# obc_old.net
KiCad netlist of a schematic drawn in EAGLE
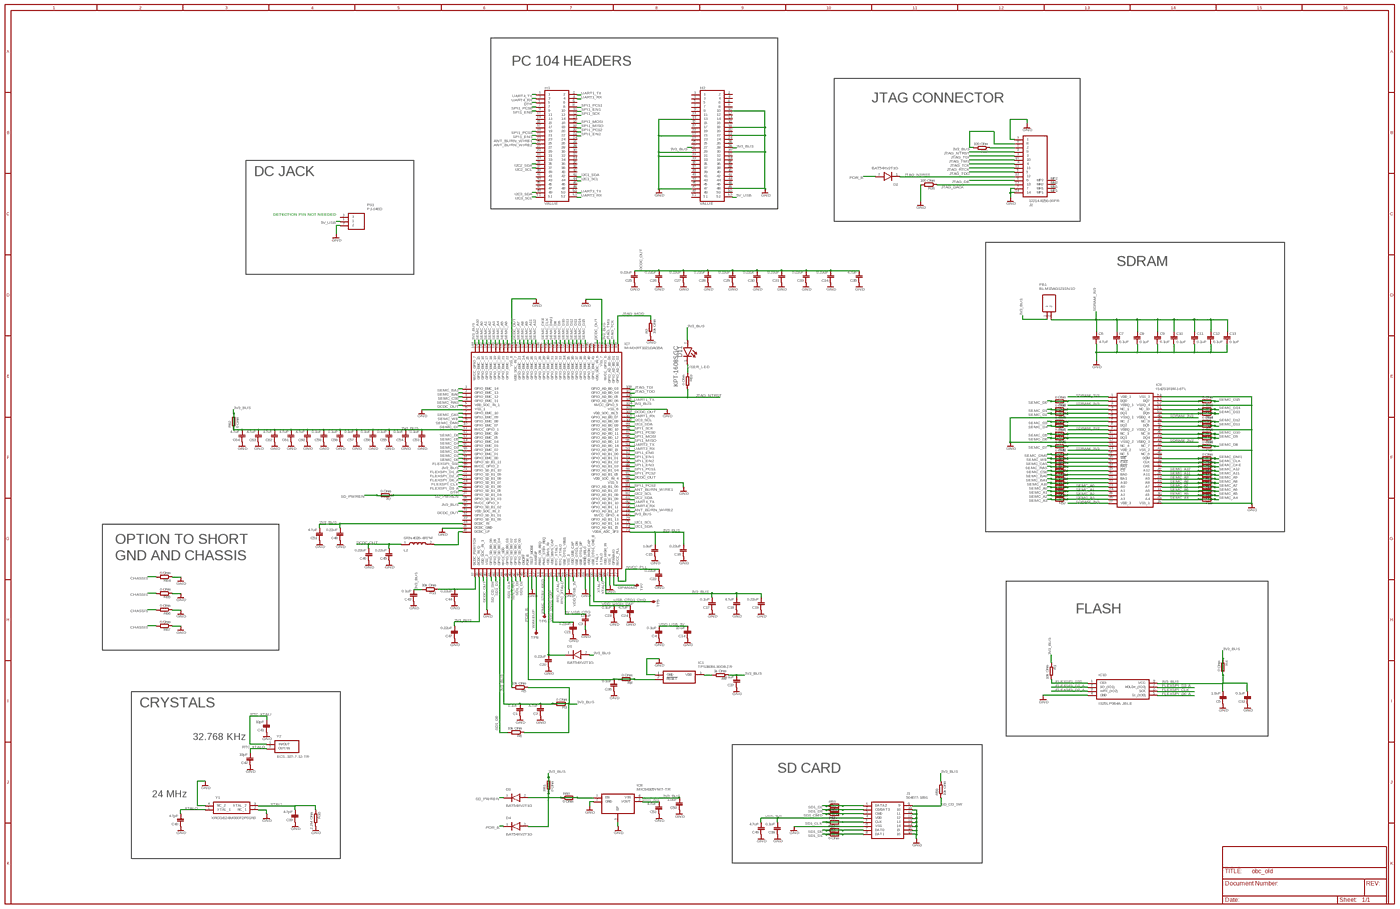
[diagram p0: schematic, sheet 1, overview]
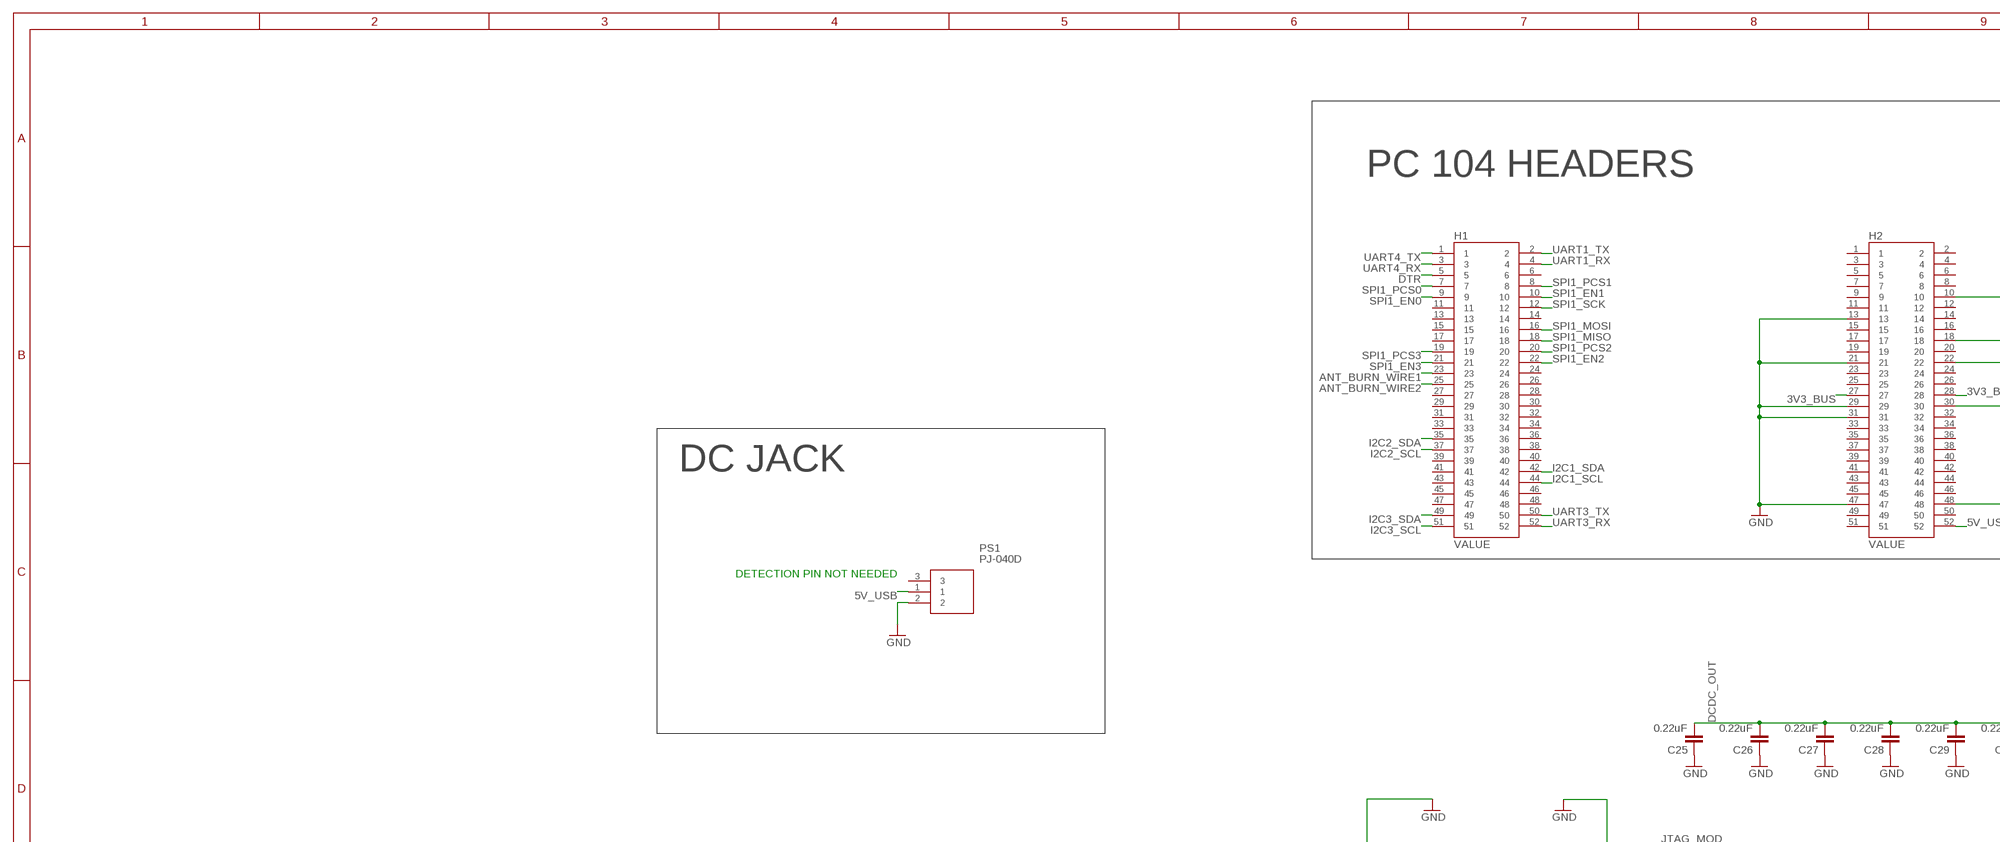
[diagram p1: schematic, sheet 1, part 1 of 4]
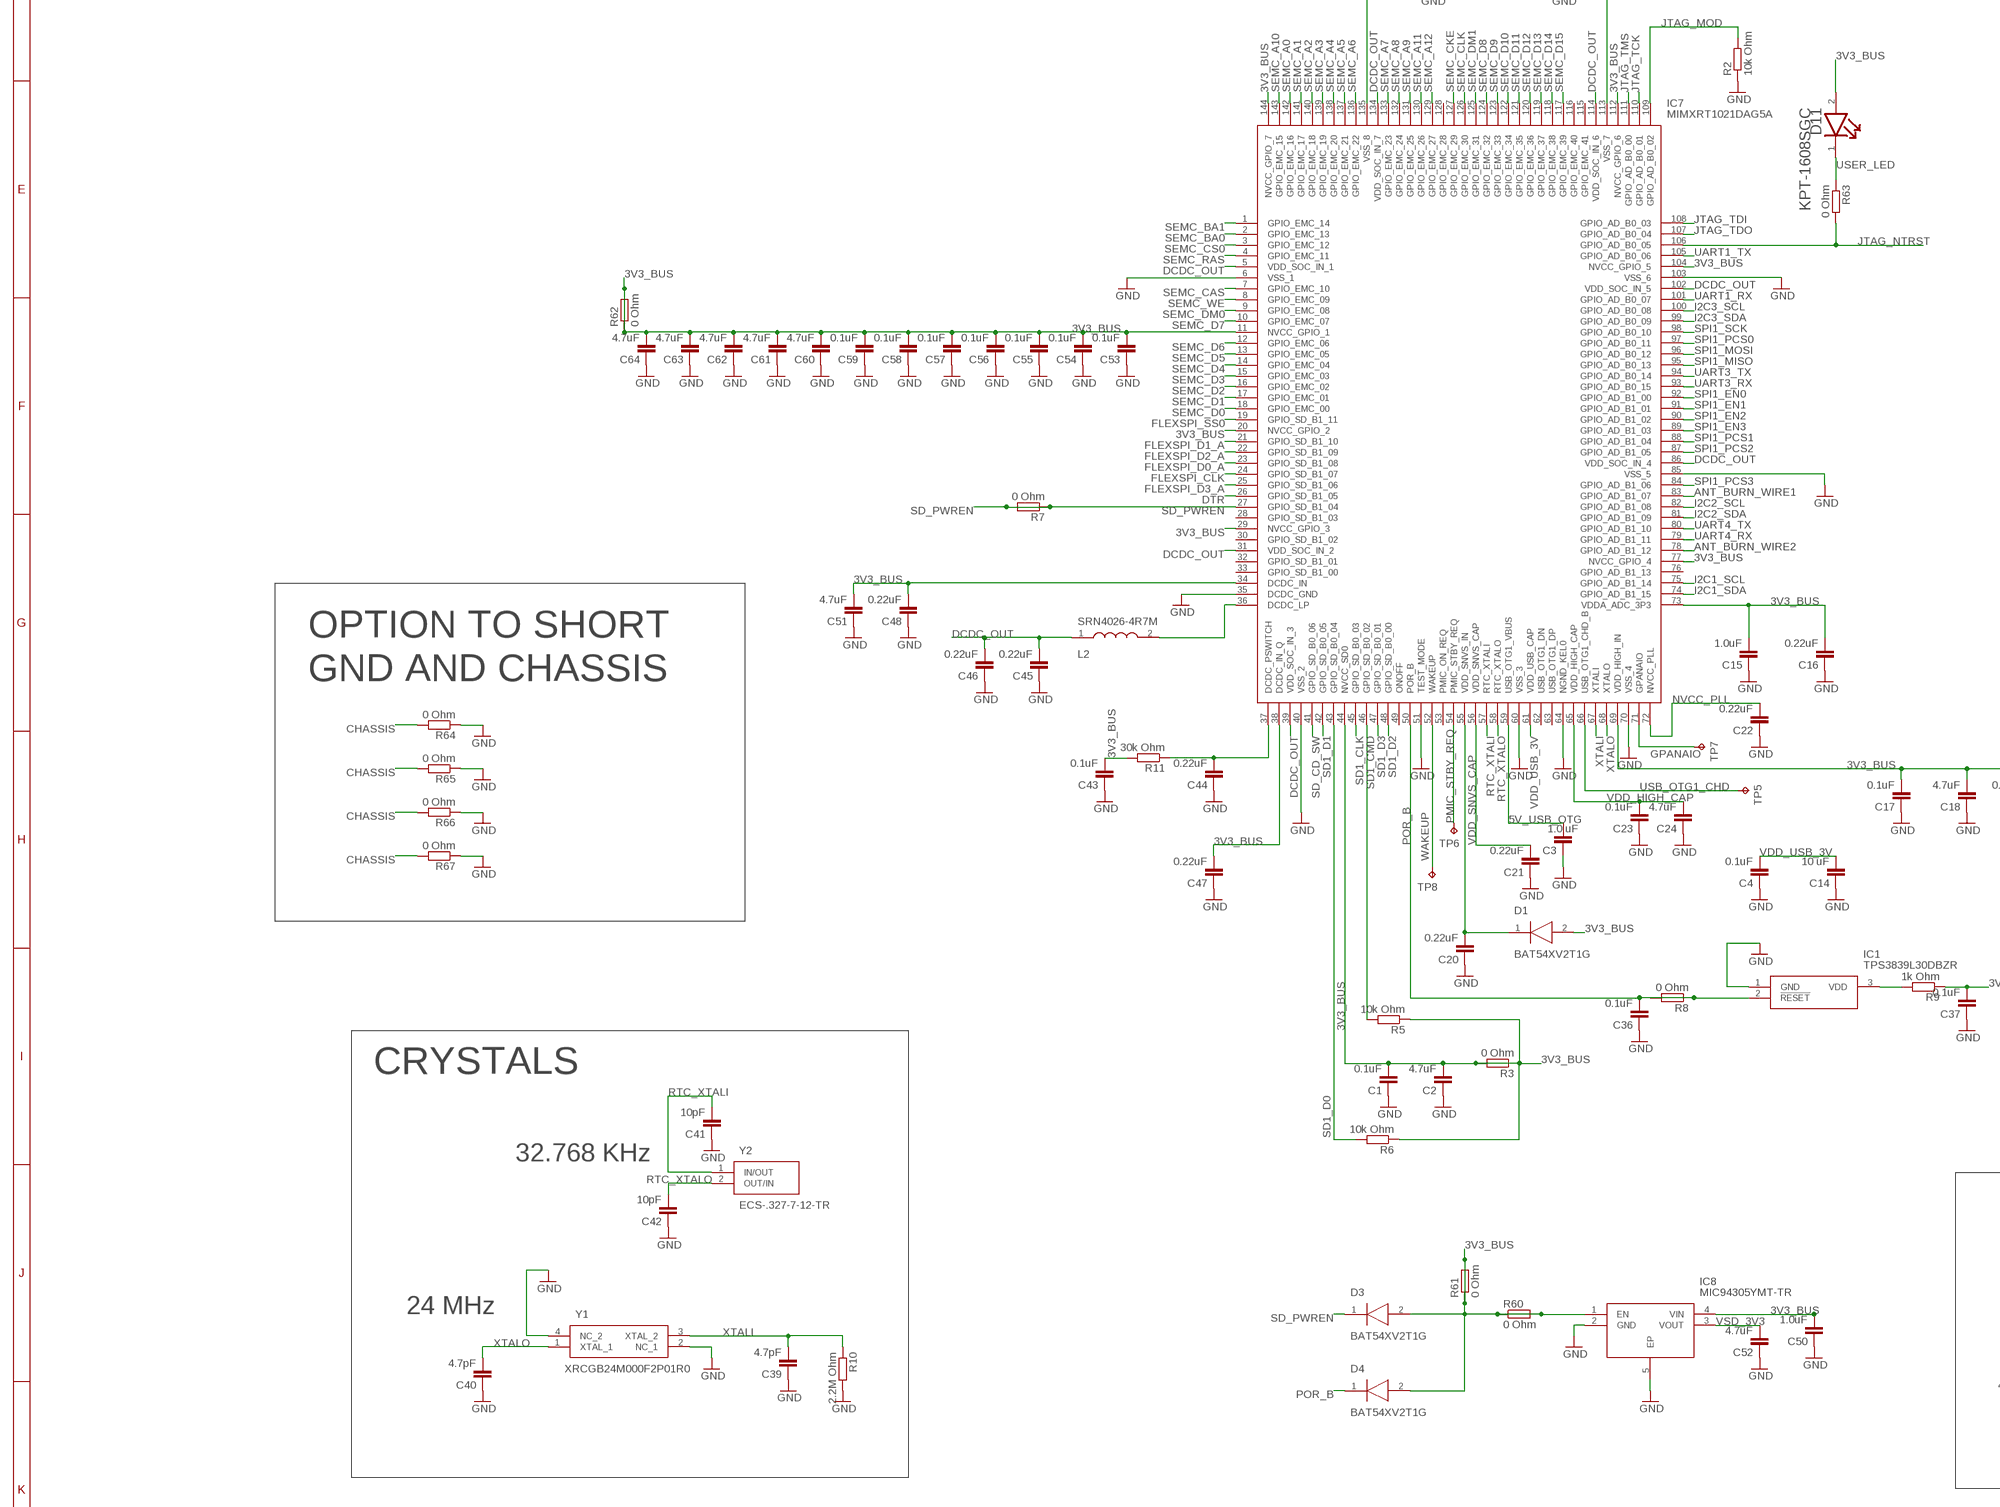
[diagram p2: schematic, sheet 1, part 2 of 4]
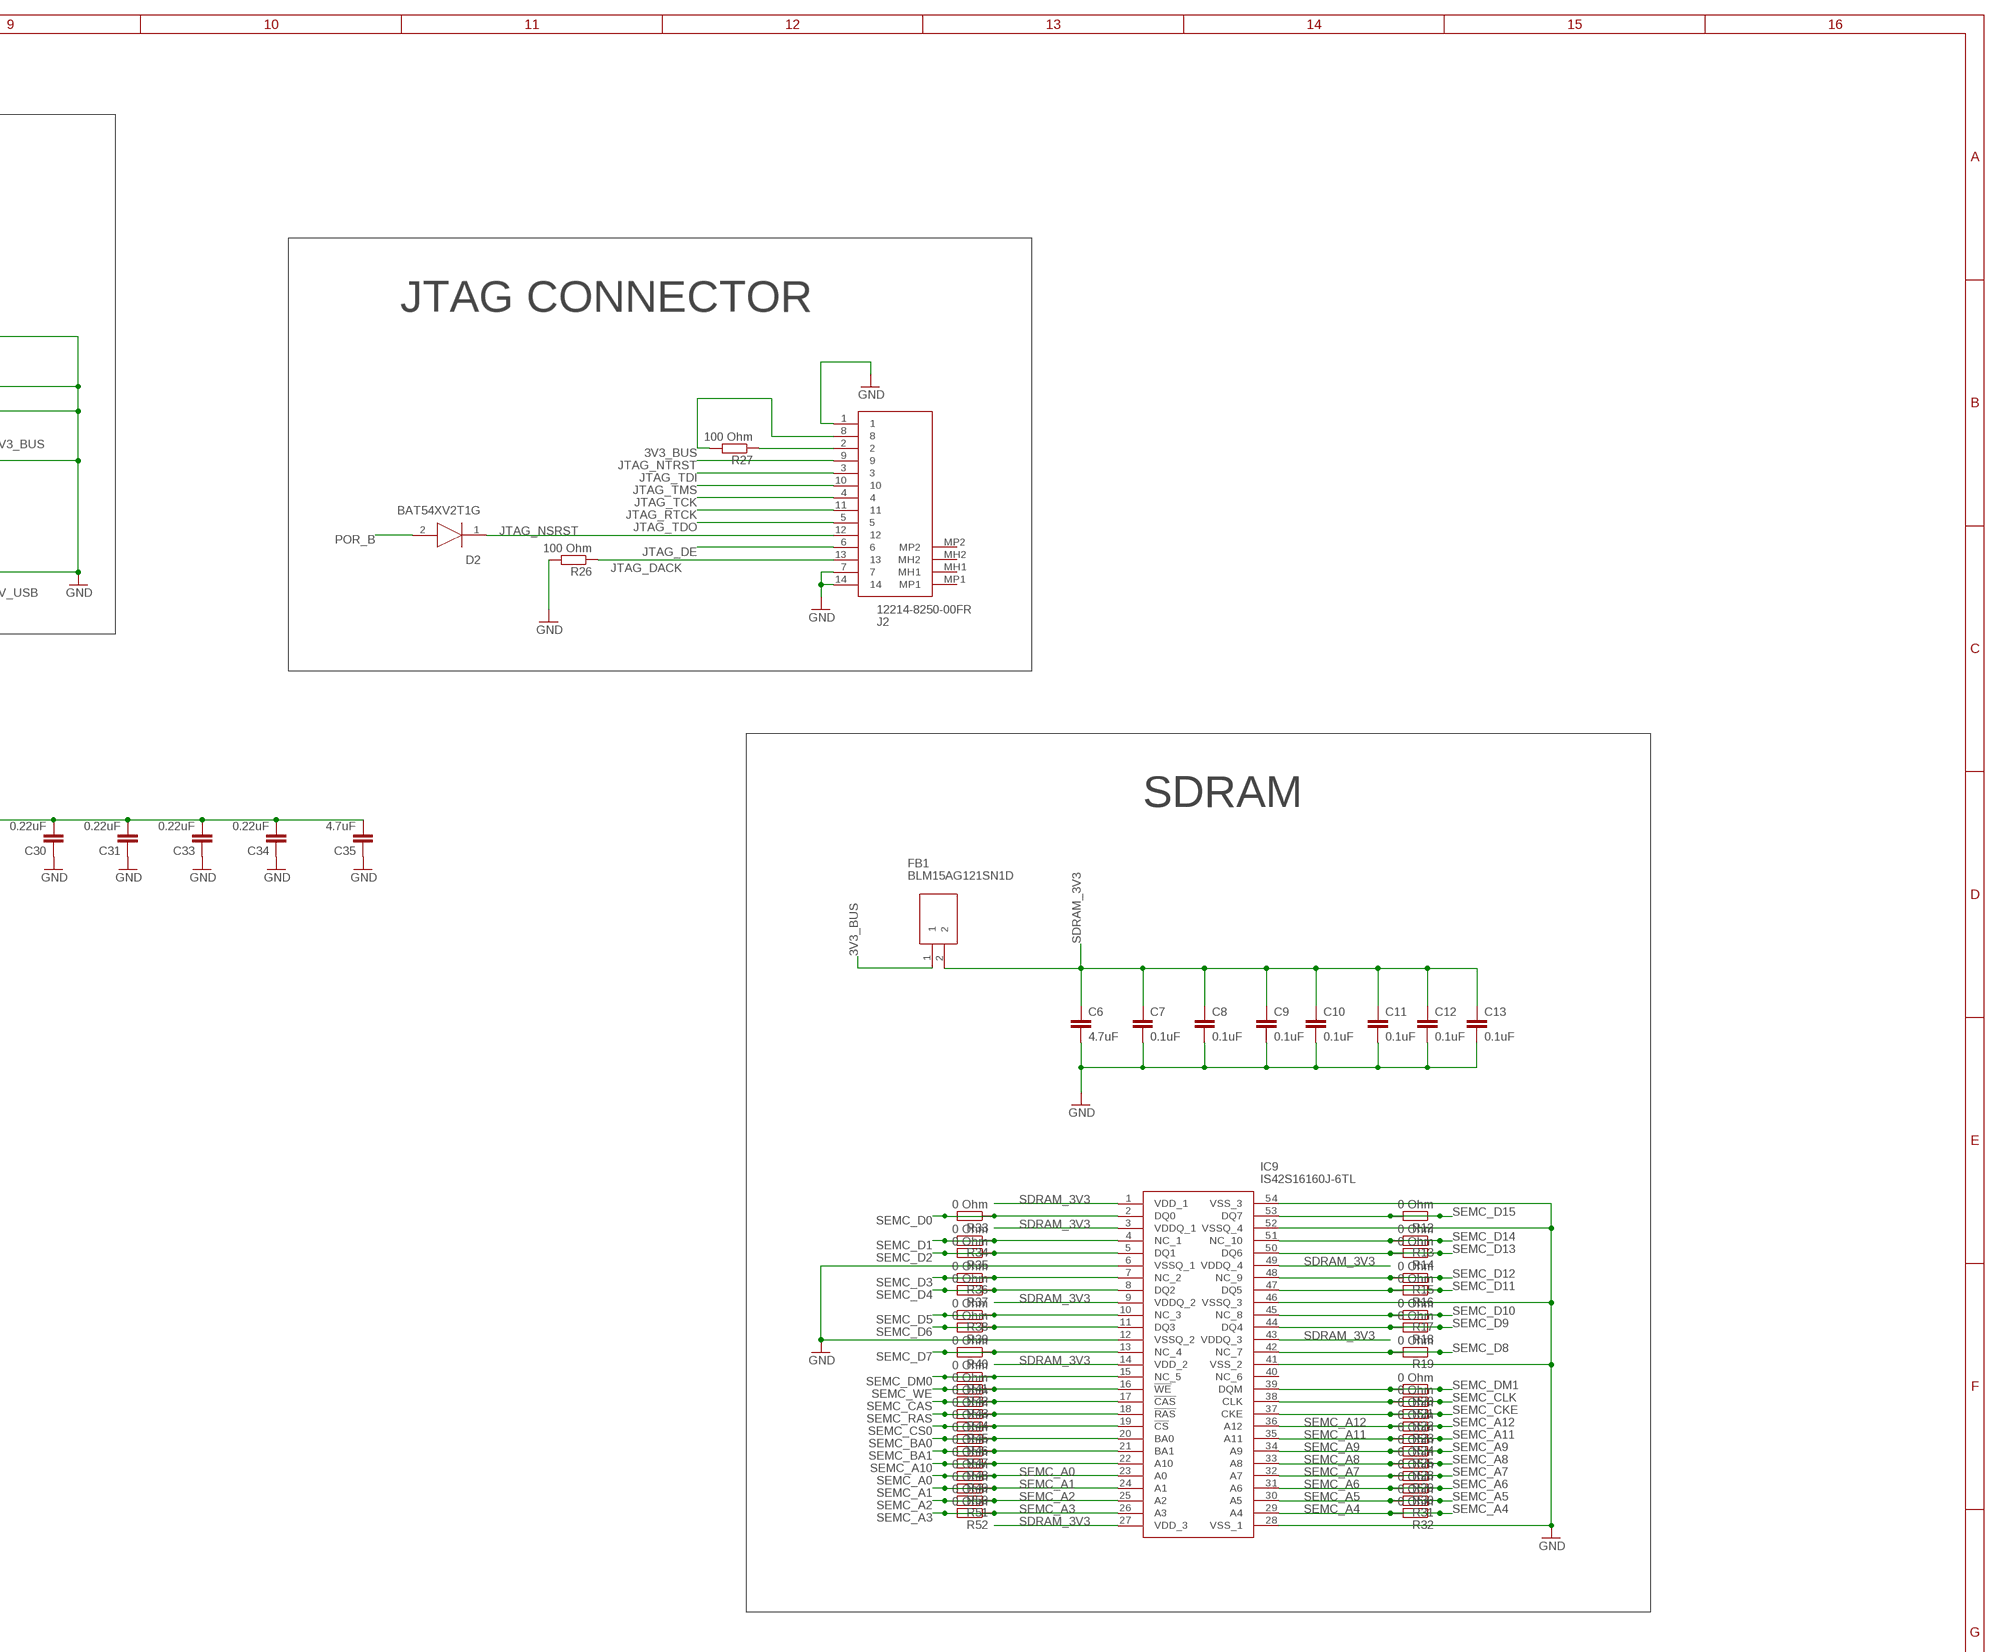
[diagram p3: schematic, sheet 1, part 3 of 4]
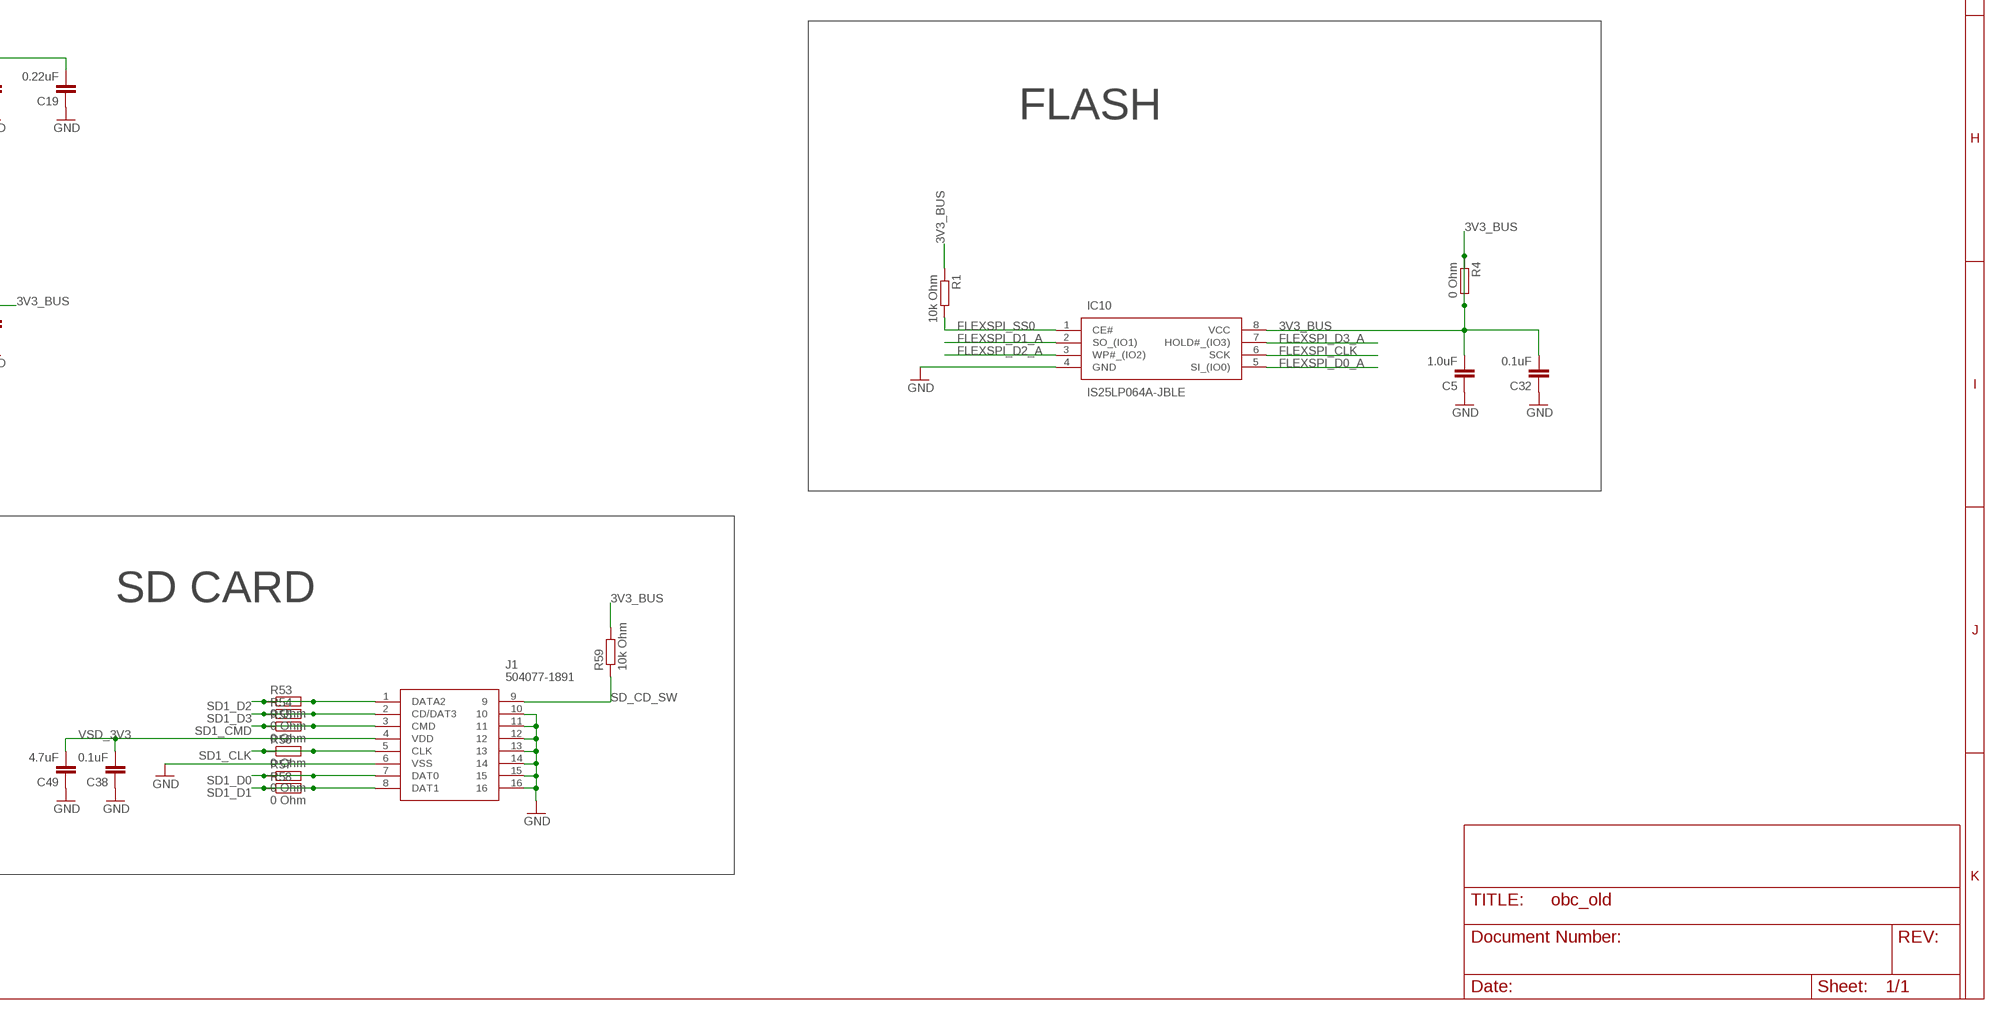
[diagram p4: schematic, sheet 1, part 4 of 4]

(export (version "E")
  (design (tool "Eeschema 10.0.6"))
  (components
    (comp (ref "C1")
      (value "0.1uF")
      (footprint "eagle-import:C0402K")
      (libsource (lib "eagle-import") (part "C-EUC0402K"))
    )
    (comp (ref "C2")
      (value "4.7uF")
      (footprint "eagle-import:C0402K")
      (libsource (lib "eagle-import") (part "C-EUC0402K"))
    )
    (comp (ref "C3")
      (value "1.0 uF")
      (footprint "eagle-import:C0402K")
      (libsource (lib "eagle-import") (part "C-EUC0402K"))
    )
    (comp (ref "C4")
      (value "0.1uF")
      (footprint "eagle-import:C0402K")
      (libsource (lib "eagle-import") (part "C-EUC0402K"))
    )
    (comp (ref "C5")
      (value "1.0uF")
      (footprint "eagle-import:C0402K")
      (libsource (lib "eagle-import") (part "C-EUC0402K"))
    )
    (comp (ref "C6")
      (value "4.7uF")
      (footprint "eagle-import:C0402K")
      (libsource (lib "eagle-import") (part "C-EUC0402K"))
    )
    (comp (ref "C7")
      (value "0.1uF")
      (footprint "eagle-import:C0402K")
      (libsource (lib "eagle-import") (part "C-EUC0402K"))
    )
    (comp (ref "C8")
      (value "0.1uF")
      (footprint "eagle-import:C0402K")
      (libsource (lib "eagle-import") (part "C-EUC0402K"))
    )
    (comp (ref "C9")
      (value "0.1uF")
      (footprint "eagle-import:C0402K")
      (libsource (lib "eagle-import") (part "C-EUC0402K"))
    )
    (comp (ref "C10")
      (value "0.1uF")
      (footprint "eagle-import:C0402K")
      (libsource (lib "eagle-import") (part "C-EUC0402K"))
    )
    (comp (ref "C11")
      (value "0.1uF")
      (footprint "eagle-import:C0402K")
      (libsource (lib "eagle-import") (part "C-EUC0402K"))
    )
    (comp (ref "C12")
      (value "0.1uF")
      (footprint "eagle-import:C0402K")
      (libsource (lib "eagle-import") (part "C-EUC0402K"))
    )
    (comp (ref "C13")
      (value "0.1uF")
      (footprint "eagle-import:C0402K")
      (libsource (lib "eagle-import") (part "C-EUC0402K"))
    )
    (comp (ref "C14")
      (value "10 uF")
      (footprint "eagle-import:C0402K")
      (libsource (lib "eagle-import") (part "C-EUC0402K"))
    )
    (comp (ref "C15")
      (value "1.0uF")
      (footprint "eagle-import:C0402K")
      (libsource (lib "eagle-import") (part "C-EUC0402K"))
    )
    (comp (ref "C16")
      (value "0.22uF")
      (footprint "eagle-import:C0402K")
      (libsource (lib "eagle-import") (part "C-EUC0402K"))
    )
    (comp (ref "C17")
      (value "0.1uF")
      (footprint "eagle-import:C0402K")
      (libsource (lib "eagle-import") (part "C-EUC0402K"))
    )
    (comp (ref "C18")
      (value "4.7uF")
      (footprint "eagle-import:C0402K")
      (libsource (lib "eagle-import") (part "C-EUC0402K"))
    )
    (comp (ref "C19")
      (value "0.22uF")
      (footprint "eagle-import:C0402K")
      (libsource (lib "eagle-import") (part "C-EUC0402K"))
    )
    (comp (ref "C20")
      (value "0.22uF")
      (footprint "eagle-import:C0402K")
      (libsource (lib "eagle-import") (part "C-EUC0402K"))
    )
    (comp (ref "C21")
      (value "0.22uF")
      (footprint "eagle-import:C0402K")
      (libsource (lib "eagle-import") (part "C-EUC0402K"))
    )
    (comp (ref "C22")
      (value "0.22uF")
      (footprint "eagle-import:C0402K")
      (libsource (lib "eagle-import") (part "C-EUC0402K"))
    )
    (comp (ref "C23")
      (value "0.1uF")
      (footprint "eagle-import:C0402K")
      (libsource (lib "eagle-import") (part "C-EUC0402K"))
    )
    (comp (ref "C24")
      (value "4.7uF")
      (footprint "eagle-import:C0402K")
      (libsource (lib "eagle-import") (part "C-EUC0402K"))
    )
    (comp (ref "C25")
      (value "0.22uF")
      (footprint "eagle-import:C0402K")
      (libsource (lib "eagle-import") (part "C-EUC0402K"))
    )
    (comp (ref "C26")
      (value "0.22uF")
      (footprint "eagle-import:C0402K")
      (libsource (lib "eagle-import") (part "C-EUC0402K"))
    )
    (comp (ref "C27")
      (value "0.22uF")
      (footprint "eagle-import:C0402K")
      (libsource (lib "eagle-import") (part "C-EUC0402K"))
    )
    (comp (ref "C28")
      (value "0.22uF")
      (footprint "eagle-import:C0402K")
      (libsource (lib "eagle-import") (part "C-EUC0402K"))
    )
    (comp (ref "C29")
      (value "0.22uF")
      (footprint "eagle-import:C0402K")
      (libsource (lib "eagle-import") (part "C-EUC0402K"))
    )
    (comp (ref "C30")
      (value "0.22uF")
      (footprint "eagle-import:C0402K")
      (libsource (lib "eagle-import") (part "C-EUC0402K"))
    )
    (comp (ref "C31")
      (value "0.22uF")
      (footprint "eagle-import:C0402K")
      (libsource (lib "eagle-import") (part "C-EUC0402K"))
    )
    (comp (ref "C32")
      (value "0.1uF")
      (footprint "eagle-import:C0402K")
      (libsource (lib "eagle-import") (part "C-EUC0402K"))
    )
    (comp (ref "C33")
      (value "0.22uF")
      (footprint "eagle-import:C0402K")
      (libsource (lib "eagle-import") (part "C-EUC0402K"))
    )
    (comp (ref "C34")
      (value "0.22uF")
      (footprint "eagle-import:C0402K")
      (libsource (lib "eagle-import") (part "C-EUC0402K"))
    )
    (comp (ref "C35")
      (value "4.7uF")
      (footprint "eagle-import:C0402K")
      (libsource (lib "eagle-import") (part "C-EUC0402K"))
    )
    (comp (ref "C36")
      (value "0.1uF")
      (footprint "eagle-import:C0402K")
      (libsource (lib "eagle-import") (part "C-EUC0402K"))
    )
    (comp (ref "C37")
      (value "0.1uF")
      (footprint "eagle-import:C0402K")
      (libsource (lib "eagle-import") (part "C-EUC0402K"))
    )
    (comp (ref "C38")
      (value "0.1uF")
      (footprint "eagle-import:C0402K")
      (libsource (lib "eagle-import") (part "C-EUC0402K"))
    )
    (comp (ref "C39")
      (value "4.7pF")
      (footprint "eagle-import:C0402K")
      (libsource (lib "eagle-import") (part "C-EUC0402K"))
    )
    (comp (ref "C40")
      (value "4.7pF")
      (footprint "eagle-import:C0402K")
      (libsource (lib "eagle-import") (part "C-EUC0402K"))
    )
    (comp (ref "C41")
      (value "10pF")
      (footprint "eagle-import:C0402K")
      (libsource (lib "eagle-import") (part "C-EUC0402K"))
    )
    (comp (ref "C42")
      (value "10pF")
      (footprint "eagle-import:C0402K")
      (libsource (lib "eagle-import") (part "C-EUC0402K"))
    )
    (comp (ref "C43")
      (value "0.1uF")
      (footprint "eagle-import:C0402K")
      (libsource (lib "eagle-import") (part "C-EUC0402K"))
    )
    (comp (ref "C44")
      (value "0.22uF")
      (footprint "eagle-import:C0402K")
      (libsource (lib "eagle-import") (part "C-EUC0402K"))
    )
    (comp (ref "C45")
      (value "0.22uF")
      (footprint "eagle-import:C0402K")
      (libsource (lib "eagle-import") (part "C-EUC0402K"))
    )
    (comp (ref "C46")
      (value "0.22uF")
      (footprint "eagle-import:C0402K")
      (libsource (lib "eagle-import") (part "C-EUC0402K"))
    )
    (comp (ref "C47")
      (value "0.22uF")
      (footprint "eagle-import:C0402K")
      (libsource (lib "eagle-import") (part "C-EUC0402K"))
    )
    (comp (ref "C48")
      (value "0.22uF")
      (footprint "eagle-import:C0402K")
      (libsource (lib "eagle-import") (part "C-EUC0402K"))
    )
    (comp (ref "C49")
      (value "4.7uF")
      (footprint "eagle-import:C0402K")
      (libsource (lib "eagle-import") (part "C-EUC0402K"))
    )
    (comp (ref "C50")
      (value "1.0uF")
      (footprint "eagle-import:C0402K")
      (libsource (lib "eagle-import") (part "C-EUC0402K"))
    )
    (comp (ref "C51")
      (value "4.7uF")
      (footprint "eagle-import:C0402K")
      (libsource (lib "eagle-import") (part "C-EUC0402K"))
    )
    (comp (ref "C52")
      (value "4.7uF")
      (footprint "eagle-import:C0402K")
      (libsource (lib "eagle-import") (part "C-EUC0402K"))
    )
    (comp (ref "C53")
      (value "0.1uF")
      (footprint "eagle-import:C0402K")
      (libsource (lib "eagle-import") (part "C-EUC0402K"))
    )
    (comp (ref "C54")
      (value "0.1uF")
      (footprint "eagle-import:C0402K")
      (libsource (lib "eagle-import") (part "C-EUC0402K"))
    )
    (comp (ref "C55")
      (value "0.1uF")
      (footprint "eagle-import:C0402K")
      (libsource (lib "eagle-import") (part "C-EUC0402K"))
    )
    (comp (ref "C56")
      (value "0.1uF")
      (footprint "eagle-import:C0402K")
      (libsource (lib "eagle-import") (part "C-EUC0402K"))
    )
    (comp (ref "C57")
      (value "0.1uF")
      (footprint "eagle-import:C0402K")
      (libsource (lib "eagle-import") (part "C-EUC0402K"))
    )
    (comp (ref "C58")
      (value "0.1uF")
      (footprint "eagle-import:C0402K")
      (libsource (lib "eagle-import") (part "C-EUC0402K"))
    )
    (comp (ref "C59")
      (value "0.1uF")
      (footprint "eagle-import:C0402K")
      (libsource (lib "eagle-import") (part "C-EUC0402K"))
    )
    (comp (ref "C60")
      (value "4.7uF")
      (footprint "eagle-import:C0402K")
      (libsource (lib "eagle-import") (part "C-EUC0402K"))
    )
    (comp (ref "C61")
      (value "4.7uF")
      (footprint "eagle-import:C0402K")
      (libsource (lib "eagle-import") (part "C-EUC0402K"))
    )
    (comp (ref "C62")
      (value "4.7uF")
      (footprint "eagle-import:C0402K")
      (libsource (lib "eagle-import") (part "C-EUC0402K"))
    )
    (comp (ref "C63")
      (value "4.7uF")
      (footprint "eagle-import:C0402K")
      (libsource (lib "eagle-import") (part "C-EUC0402K"))
    )
    (comp (ref "C64")
      (value "4.7uF")
      (footprint "eagle-import:C0402K")
      (libsource (lib "eagle-import") (part "C-EUC0402K"))
    )
    (comp (ref "D1")
      (value "BAT54XV2T1G")
      (footprint "eagle-import:SODFL1608X70N")
      (fields (field (name "MOUSER_PART_NUMBER") "863-BAT54XV2T1G"))
      (libsource (lib "eagle-import") (part "BAT54XV2T1G"))
    )
    (comp (ref "D2")
      (value "BAT54XV2T1G")
      (footprint "eagle-import:SODFL1608X70N")
      (fields (field (name "MOUSER_PART_NUMBER") "863-BAT54XV2T1G"))
      (libsource (lib "eagle-import") (part "BAT54XV2T1G"))
    )
    (comp (ref "D3")
      (value "BAT54XV2T1G")
      (footprint "eagle-import:SODFL1608X70N")
      (fields (field (name "MOUSER_PART_NUMBER") "863-BAT54XV2T1G"))
      (libsource (lib "eagle-import") (part "BAT54XV2T1G"))
    )
    (comp (ref "D4")
      (value "BAT54XV2T1G")
      (footprint "eagle-import:SODFL1608X70N")
      (fields (field (name "MOUSER_PART_NUMBER") "863-BAT54XV2T1G"))
      (libsource (lib "eagle-import") (part "BAT54XV2T1G"))
    )
    (comp (ref "D11")
      (value "KINGBRIGHT_KPT-1608SGCKINGBRIGHT_KPT-1608SGC_0_0")
      (footprint "eagle-import:KINGBRIGHT_KPT-1608SGC_0")
      (fields (field (name "MF") "Kingbright") (field (name "MPN") "KPT-1608SGC"))
      (libsource (lib "eagle-import") (part "KINGBRIGHT_KPT-1608SGCKINGBRIGHT_KPT-1608SGC_0_0"))
    )
    (comp (ref "FB1")
      (value "BLM15AG121SN1D")
      (footprint "eagle-import:NFZ15SG152SN10B")
      (fields (field (name "MOUSER_PART_NUMBER") "81-BLM15AG121SN1D"))
      (libsource (lib "eagle-import") (part "BLM15AG121SN1D"))
    )
    (comp (ref "H1")
      (value "ESQ-126-39-G-D")
      (footprint "eagle-import:SAMTEC_ESQ-126-39-G-D")
      (fields (field (name "DIGI-KEY_PART_NUMBER") "SAM10462-ND") (field (name "MF") "Samtec"))
      (libsource (lib "eagle-import") (part "ESQ-126-39-G-D"))
    )
    (comp (ref "H2")
      (value "ESQ-126-39-G-D")
      (footprint "eagle-import:SAMTEC_ESQ-126-39-G-D")
      (fields (field (name "DIGI-KEY_PART_NUMBER") "SAM10462-ND") (field (name "MF") "Samtec"))
      (libsource (lib "eagle-import") (part "ESQ-126-39-G-D"))
    )
    (comp (ref "IC1")
      (value "TPS3839L30DBZR")
      (footprint "eagle-import:SOT95P237X112-3N")
      (fields (field (name "MOUSER_PART_NUMBER") "595-TPS3839L30DBZR"))
      (libsource (lib "eagle-import") (part "TPS3839L30DBZR"))
    )
    (comp (ref "IC7")
      (value "MIMXRT1021DAG5A")
      (footprint "eagle-import:QFP50P2200X2200X160-144N")
      (fields (field (name "MOUSER_PART_NUMBER") "771-MIMXRT1021DAG5A"))
      (libsource (lib "eagle-import") (part "MIMXRT1021DAG5A"))
    )
    (comp (ref "IC8")
      (value "MIC94305YMT-TR")
      (footprint "eagle-import:SON50P160X120X60-5N")
      (fields (field (name "MOUSER_PART_NUMBER") "998-MIC94305YMTTR"))
      (libsource (lib "eagle-import") (part "MIC94305YMT-TR"))
    )
    (comp (ref "IC9")
      (value "IS42S16160J-6TL")
      (footprint "eagle-import:SOP80P1176X120-54N")
      (fields (field (name "MOUSER_PART_NUMBER") "870-IS42S16160J-6TL"))
      (libsource (lib "eagle-import") (part "IS42S16160J-6TL"))
    )
    (comp (ref "IC10")
      (value "IS25LP064A-JBLE")
      (footprint "eagle-import:SOIC127P790X216-8N")
      (libsource (lib "eagle-import") (part "IS25LP064A-JBLE"))
    )
    (comp (ref "J1")
      (value "504077-1891")
      (footprint "eagle-import:5040771891")
      (fields (field (name "MOUSER_PART_NUMBER") "538-504077-1891"))
      (libsource (lib "eagle-import") (part "504077-1891"))
    )
    (comp (ref "J2")
      (value "12214-8250-00FR")
      (footprint "eagle-import:12214825000FR")
      (fields (field (name "MOUSER_PART_NUMBER") "517-12214-825000FR"))
      (libsource (lib "eagle-import") (part "12214-8250-00FR"))
    )
    (comp (ref "L2")
      (value "SRN4026-4R7M")
      (footprint "eagle-import:SRN4026")
      (fields (field (name "MOUSER_PART_NUMBER") "652-SRN4026-4R7M"))
      (libsource (lib "eagle-import") (part "SRN4026-4R7M"))
    )
    (comp (ref "PS1")
      (value "PJ-040D")
      (footprint "eagle-import:PJ040D")
      (fields (field (name "MOUSER_PART_NUMBER") "490-PJ-040D"))
      (libsource (lib "eagle-import") (part "PJ-040D"))
    )
    (comp (ref "R1")
      (value "10k Ohm")
      (footprint "eagle-import:R0402")
      (libsource (lib "eagle-import") (part "R-EU_R0402"))
    )
    (comp (ref "R2")
      (value "10k Ohm")
      (footprint "eagle-import:R0402")
      (libsource (lib "eagle-import") (part "R-EU_R0402"))
    )
    (comp (ref "R3")
      (value "0 Ohm")
      (footprint "eagle-import:R0402")
      (libsource (lib "eagle-import") (part "R-EU_R0402"))
    )
    (comp (ref "R4")
      (value "0 Ohm")
      (footprint "eagle-import:R0402")
      (libsource (lib "eagle-import") (part "R-EU_R0402"))
    )
    (comp (ref "R5")
      (value "10k Ohm")
      (footprint "eagle-import:R0402")
      (libsource (lib "eagle-import") (part "R-EU_R0402"))
    )
    (comp (ref "R6")
      (value "10k Ohm")
      (footprint "eagle-import:R0402")
      (libsource (lib "eagle-import") (part "R-EU_R0402"))
    )
    (comp (ref "R7")
      (value "0 Ohm")
      (footprint "eagle-import:R0402")
      (libsource (lib "eagle-import") (part "R-EU_R0402"))
    )
    (comp (ref "R8")
      (value "0 Ohm")
      (footprint "eagle-import:R0402")
      (libsource (lib "eagle-import") (part "R-EU_R0402"))
    )
    (comp (ref "R9")
      (value "1k Ohm")
      (footprint "eagle-import:R0402")
      (libsource (lib "eagle-import") (part "R-EU_R0402"))
    )
    (comp (ref "R10")
      (value "2.2M Ohm")
      (footprint "eagle-import:R0402")
      (libsource (lib "eagle-import") (part "R-EU_R0402"))
    )
    (comp (ref "R11")
      (value "30k Ohm")
      (footprint "eagle-import:R0402")
      (libsource (lib "eagle-import") (part "R-EU_R0402"))
    )
    (comp (ref "R12")
      (value "0 Ohm")
      (footprint "eagle-import:R0402")
      (libsource (lib "eagle-import") (part "R-EU_R0402"))
    )
    (comp (ref "R13")
      (value "0 Ohm")
      (footprint "eagle-import:R0402")
      (libsource (lib "eagle-import") (part "R-EU_R0402"))
    )
    (comp (ref "R14")
      (value "0 Ohm")
      (footprint "eagle-import:R0402")
      (libsource (lib "eagle-import") (part "R-EU_R0402"))
    )
    (comp (ref "R15")
      (value "0 Ohm")
      (footprint "eagle-import:R0402")
      (libsource (lib "eagle-import") (part "R-EU_R0402"))
    )
    (comp (ref "R16")
      (value "0 Ohm")
      (footprint "eagle-import:R0402")
      (libsource (lib "eagle-import") (part "R-EU_R0402"))
    )
    (comp (ref "R17")
      (value "0 Ohm")
      (footprint "eagle-import:R0402")
      (libsource (lib "eagle-import") (part "R-EU_R0402"))
    )
    (comp (ref "R18")
      (value "0 Ohm")
      (footprint "eagle-import:R0402")
      (libsource (lib "eagle-import") (part "R-EU_R0402"))
    )
    (comp (ref "R19")
      (value "0 Ohm")
      (footprint "eagle-import:R0402")
      (libsource (lib "eagle-import") (part "R-EU_R0402"))
    )
    (comp (ref "R20")
      (value "0 Ohm")
      (footprint "eagle-import:R0402")
      (libsource (lib "eagle-import") (part "R-EU_R0402"))
    )
    (comp (ref "R21")
      (value "0 Ohm")
      (footprint "eagle-import:R0402")
      (libsource (lib "eagle-import") (part "R-EU_R0402"))
    )
    (comp (ref "R22")
      (value "0 Ohm")
      (footprint "eagle-import:R0402")
      (libsource (lib "eagle-import") (part "R-EU_R0402"))
    )
    (comp (ref "R23")
      (value "0 Ohm")
      (footprint "eagle-import:R0402")
      (libsource (lib "eagle-import") (part "R-EU_R0402"))
    )
    (comp (ref "R24")
      (value "0 Ohm")
      (footprint "eagle-import:R0402")
      (libsource (lib "eagle-import") (part "R-EU_R0402"))
    )
    (comp (ref "R25")
      (value "0 Ohm")
      (footprint "eagle-import:R0402")
      (libsource (lib "eagle-import") (part "R-EU_R0402"))
    )
    (comp (ref "R26")
      (value "100 Ohm")
      (footprint "eagle-import:R0402")
      (libsource (lib "eagle-import") (part "R-EU_R0402"))
    )
    (comp (ref "R27")
      (value "100 Ohm")
      (footprint "eagle-import:R0402")
      (libsource (lib "eagle-import") (part "R-EU_R0402"))
    )
    (comp (ref "R28")
      (value "0 Ohm")
      (footprint "eagle-import:R0402")
      (libsource (lib "eagle-import") (part "R-EU_R0402"))
    )
    (comp (ref "R29")
      (value "0 Ohm")
      (footprint "eagle-import:R0402")
      (libsource (lib "eagle-import") (part "R-EU_R0402"))
    )
    (comp (ref "R30")
      (value "0 Ohm")
      (footprint "eagle-import:R0402")
      (libsource (lib "eagle-import") (part "R-EU_R0402"))
    )
    (comp (ref "R31")
      (value "0 Ohm")
      (footprint "eagle-import:R0402")
      (libsource (lib "eagle-import") (part "R-EU_R0402"))
    )
    (comp (ref "R32")
      (value "0 Ohm")
      (footprint "eagle-import:R0402")
      (libsource (lib "eagle-import") (part "R-EU_R0402"))
    )
    (comp (ref "R33")
      (value "0 Ohm")
      (footprint "eagle-import:R0402")
      (libsource (lib "eagle-import") (part "R-EU_R0402"))
    )
    (comp (ref "R34")
      (value "0 Ohm")
      (footprint "eagle-import:R0402")
      (libsource (lib "eagle-import") (part "R-EU_R0402"))
    )
    (comp (ref "R35")
      (value "0 Ohm")
      (footprint "eagle-import:R0402")
      (libsource (lib "eagle-import") (part "R-EU_R0402"))
    )
    (comp (ref "R36")
      (value "0 Ohm")
      (footprint "eagle-import:R0402")
      (libsource (lib "eagle-import") (part "R-EU_R0402"))
    )
    (comp (ref "R37")
      (value "0 Ohm")
      (footprint "eagle-import:R0402")
      (libsource (lib "eagle-import") (part "R-EU_R0402"))
    )
    (comp (ref "R38")
      (value "0 Ohm")
      (footprint "eagle-import:R0402")
      (libsource (lib "eagle-import") (part "R-EU_R0402"))
    )
    (comp (ref "R39")
      (value "0 Ohm")
      (footprint "eagle-import:R0402")
      (libsource (lib "eagle-import") (part "R-EU_R0402"))
    )
    (comp (ref "R40")
      (value "0 Ohm")
      (footprint "eagle-import:R0402")
      (libsource (lib "eagle-import") (part "R-EU_R0402"))
    )
    (comp (ref "R41")
      (value "0 Ohm")
      (footprint "eagle-import:R0402")
      (libsource (lib "eagle-import") (part "R-EU_R0402"))
    )
    (comp (ref "R42")
      (value "0 Ohm")
      (footprint "eagle-import:R0402")
      (libsource (lib "eagle-import") (part "R-EU_R0402"))
    )
    (comp (ref "R43")
      (value "0 Ohm")
      (footprint "eagle-import:R0402")
      (libsource (lib "eagle-import") (part "R-EU_R0402"))
    )
    (comp (ref "R44")
      (value "0 Ohm")
      (footprint "eagle-import:R0402")
      (libsource (lib "eagle-import") (part "R-EU_R0402"))
    )
    (comp (ref "R45")
      (value "0 Ohm")
      (footprint "eagle-import:R0402")
      (libsource (lib "eagle-import") (part "R-EU_R0402"))
    )
    (comp (ref "R46")
      (value "0 Ohm")
      (footprint "eagle-import:R0402")
      (libsource (lib "eagle-import") (part "R-EU_R0402"))
    )
    (comp (ref "R47")
      (value "0 Ohm")
      (footprint "eagle-import:R0402")
      (libsource (lib "eagle-import") (part "R-EU_R0402"))
    )
    (comp (ref "R48")
      (value "0 Ohm")
      (footprint "eagle-import:R0402")
      (libsource (lib "eagle-import") (part "R-EU_R0402"))
    )
    (comp (ref "R49")
      (value "0 Ohm")
      (footprint "eagle-import:R0402")
      (libsource (lib "eagle-import") (part "R-EU_R0402"))
    )
    (comp (ref "R50")
      (value "0 Ohm")
      (footprint "eagle-import:R0402")
      (libsource (lib "eagle-import") (part "R-EU_R0402"))
    )
    (comp (ref "R51")
      (value "0 Ohm")
      (footprint "eagle-import:R0402")
      (libsource (lib "eagle-import") (part "R-EU_R0402"))
    )
    (comp (ref "R52")
      (value "0 Ohm")
      (footprint "eagle-import:R0402")
      (libsource (lib "eagle-import") (part "R-EU_R0402"))
    )
    (comp (ref "R53")
      (value "0 Ohm")
      (footprint "eagle-import:R0402")
      (libsource (lib "eagle-import") (part "R-EU_R0402"))
    )
    (comp (ref "R54")
      (value "0 Ohm")
      (footprint "eagle-import:R0402")
      (libsource (lib "eagle-import") (part "R-EU_R0402"))
    )
    (comp (ref "R55")
      (value "0 Ohm")
      (footprint "eagle-import:R0402")
      (libsource (lib "eagle-import") (part "R-EU_R0402"))
    )
    (comp (ref "R56")
      (value "0 Ohm")
      (footprint "eagle-import:R0402")
      (libsource (lib "eagle-import") (part "R-EU_R0402"))
    )
    (comp (ref "R57")
      (value "0 Ohm")
      (footprint "eagle-import:R0402")
      (libsource (lib "eagle-import") (part "R-EU_R0402"))
    )
    (comp (ref "R58")
      (value "0 Ohm")
      (footprint "eagle-import:R0402")
      (libsource (lib "eagle-import") (part "R-EU_R0402"))
    )
    (comp (ref "R59")
      (value "10k Ohm")
      (footprint "eagle-import:R0402")
      (libsource (lib "eagle-import") (part "R-EU_R0402"))
    )
    (comp (ref "R60")
      (value "0 Ohm")
      (footprint "eagle-import:R0402")
      (libsource (lib "eagle-import") (part "R-EU_R0402"))
    )
    (comp (ref "R61")
      (value "0 Ohm")
      (footprint "eagle-import:R0402")
      (libsource (lib "eagle-import") (part "R-EU_R0402"))
    )
    (comp (ref "R62")
      (value "0 Ohm")
      (footprint "eagle-import:R0402")
      (libsource (lib "eagle-import") (part "R-EU_R0402"))
    )
    (comp (ref "R63")
      (value "0 Ohm")
      (footprint "eagle-import:R0402")
      (libsource (lib "eagle-import") (part "R-EU_R0402"))
    )
    (comp (ref "R64")
      (value "0 Ohm")
      (footprint "eagle-import:R0402")
      (libsource (lib "eagle-import") (part "R-EU_R0402"))
    )
    (comp (ref "R65")
      (value "0 Ohm")
      (footprint "eagle-import:R0402")
      (libsource (lib "eagle-import") (part "R-EU_R0402"))
    )
    (comp (ref "R66")
      (value "0 Ohm")
      (footprint "eagle-import:R0402")
      (libsource (lib "eagle-import") (part "R-EU_R0402"))
    )
    (comp (ref "R67")
      (value "0 Ohm")
      (footprint "eagle-import:R0402")
      (libsource (lib "eagle-import") (part "R-EU_R0402"))
    )
    (comp (ref "TP5")
      (value "TPTP06R")
      (footprint "eagle-import:TP06R")
      (libsource (lib "eagle-import") (part "TPTP06R"))
    )
    (comp (ref "TP6")
      (value "TPTP06R")
      (footprint "eagle-import:TP06R")
      (libsource (lib "eagle-import") (part "TPTP06R"))
    )
    (comp (ref "TP7")
      (value "TPTP06R")
      (footprint "eagle-import:TP06R")
      (libsource (lib "eagle-import") (part "TPTP06R"))
    )
    (comp (ref "TP8")
      (value "TPTP06R")
      (footprint "eagle-import:TP06R")
      (libsource (lib "eagle-import") (part "TPTP06R"))
    )
    (comp (ref "Y1")
      (value "XRCGB24M000F2P01R0")
      (footprint "eagle-import:XRCGB24M000F2P01R0")
      (fields (field (name "MOUSER_PART_NUMBER") "81-XRCGB24M000F2P01R"))
      (libsource (lib "eagle-import") (part "XRCGB24M000F2P01R0"))
    )
    (comp (ref "Y2")
      (value "ECS-.327-7-12-TR")
      (footprint "eagle-import:ECS327712TR")
      (fields (field (name "MOUSER_PART_NUMBER") "520-ECS-.327-7-12-TR"))
      (libsource (lib "eagle-import") (part "ECS-.327-7-12-TR"))
    )
  )
  (nets
    (net (code "1") (name "/3V3_BUS") (class "Default")
      (node (ref "C1") (pin "2") (pinfunction "2_2") (pintype "passive"))
      (node (ref "C15") (pin "2") (pinfunction "2_2") (pintype "passive"))
      (node (ref "C16") (pin "2") (pinfunction "2_2") (pintype "passive"))
      (node (ref "C17") (pin "2") (pinfunction "2_2") (pintype "passive"))
      (node (ref "C18") (pin "2") (pinfunction "2_2") (pintype "passive"))
      (node (ref "C19") (pin "2") (pinfunction "2_2") (pintype "passive"))
      (node (ref "C2") (pin "2") (pinfunction "2_2") (pintype "passive"))
      (node (ref "C32") (pin "2") (pinfunction "2_2") (pintype "passive"))
      (node (ref "C37") (pin "2") (pinfunction "2_2") (pintype "passive"))
      (node (ref "C43") (pin "2") (pinfunction "2_2") (pintype "passive"))
      (node (ref "C47") (pin "2") (pinfunction "2_2") (pintype "passive"))
      (node (ref "C48") (pin "2") (pinfunction "2_2") (pintype "passive"))
      (node (ref "C5") (pin "2") (pinfunction "2_2") (pintype "passive"))
      (node (ref "C50") (pin "2") (pinfunction "2_2") (pintype "passive"))
      (node (ref "C51") (pin "2") (pinfunction "2_2") (pintype "passive"))
      (node (ref "C53") (pin "2") (pinfunction "2_2") (pintype "passive"))
      (node (ref "C54") (pin "2") (pinfunction "2_2") (pintype "passive"))
      (node (ref "C55") (pin "2") (pinfunction "2_2") (pintype "passive"))
      (node (ref "C56") (pin "2") (pinfunction "2_2") (pintype "passive"))
      (node (ref "C57") (pin "2") (pinfunction "2_2") (pintype "passive"))
      (node (ref "C58") (pin "2") (pinfunction "2_2") (pintype "passive"))
      (node (ref "C59") (pin "2") (pinfunction "2_2") (pintype "passive"))
      (node (ref "C60") (pin "2") (pinfunction "2_2") (pintype "passive"))
      (node (ref "C61") (pin "2") (pinfunction "2_2") (pintype "passive"))
      (node (ref "C62") (pin "2") (pinfunction "2_2") (pintype "passive"))
      (node (ref "C63") (pin "2") (pinfunction "2_2") (pintype "passive"))
      (node (ref "C64") (pin "2") (pinfunction "2_2") (pintype "passive"))
      (node (ref "D1") (pin "2") (pinfunction "A_2") (pintype "bidirectional"))
      (node (ref "D11") (pin "2") (pinfunction "ANODE_2") (pintype "passive"))
      (node (ref "D3") (pin "2") (pinfunction "A_2") (pintype "bidirectional"))
      (node (ref "D4") (pin "2") (pinfunction "A_2") (pintype "bidirectional"))
      (node (ref "FB1") (pin "1") (pinfunction "1_1") (pintype "bidirectional"))
      (node (ref "H2") (pin "27") (pinfunction "27_27") (pintype "passive"))
      (node (ref "H2") (pin "28") (pinfunction "28_28") (pintype "passive"))
      (node (ref "IC10") (pin "8") (pinfunction "VCC_8") (pintype "bidirectional"))
      (node (ref "IC7") (pin "104") (pinfunction "NVCC_GPIO_5_104") (pintype "bidirectional"))
      (node (ref "IC7") (pin "11") (pinfunction "NVCC_GPIO_1_11") (pintype "bidirectional"))
      (node (ref "IC7") (pin "112") (pinfunction "NVCC_GPIO_6_112") (pintype "bidirectional"))
      (node (ref "IC7") (pin "144") (pinfunction "NVCC_GPIO_7_144") (pintype "bidirectional"))
      (node (ref "IC7") (pin "20") (pinfunction "NVCC_GPIO_2_20") (pintype "bidirectional"))
      (node (ref "IC7") (pin "29") (pinfunction "NVCC_GPIO_3_29") (pintype "bidirectional"))
      (node (ref "IC7") (pin "34") (pinfunction "DCDC_IN_34") (pintype "bidirectional"))
      (node (ref "IC7") (pin "38") (pinfunction "DCDC_IN_Q_38") (pintype "bidirectional"))
      (node (ref "IC7") (pin "44") (pinfunction "NVCC_SD0_44") (pintype "bidirectional"))
      (node (ref "IC7") (pin "69") (pinfunction "VDD_HIGH_IN_69") (pintype "bidirectional"))
      (node (ref "IC7") (pin "73") (pinfunction "VDDA_ADC_3P3_73") (pintype "bidirectional"))
      (node (ref "IC7") (pin "77") (pinfunction "NVCC_GPIO_4_77") (pintype "bidirectional"))
      (node (ref "IC8") (pin "1") (pinfunction "EN_1") (pintype "bidirectional"))
      (node (ref "IC8") (pin "4") (pinfunction "VIN_4") (pintype "bidirectional"))
      (node (ref "J2") (pin "8") (pinfunction "8_8") (pintype "bidirectional"))
      (node (ref "R1") (pin "1") (pinfunction "1_1") (pintype "passive"))
      (node (ref "R11") (pin "2") (pinfunction "2_2") (pintype "passive"))
      (node (ref "R27") (pin "2") (pinfunction "2_2") (pintype "passive"))
      (node (ref "R3") (pin "1") (pinfunction "1_1") (pintype "passive"))
      (node (ref "R3") (pin "2") (pinfunction "2_2") (pintype "passive"))
      (node (ref "R4") (pin "1") (pinfunction "1_1") (pintype "passive"))
      (node (ref "R4") (pin "2") (pinfunction "2_2") (pintype "passive"))
      (node (ref "R5") (pin "1") (pinfunction "1_1") (pintype "passive"))
      (node (ref "R59") (pin "2") (pinfunction "2_2") (pintype "passive"))
      (node (ref "R6") (pin "1") (pinfunction "1_1") (pintype "passive"))
      (node (ref "R60") (pin "1") (pinfunction "1_1") (pintype "passive"))
      (node (ref "R60") (pin "2") (pinfunction "2_2") (pintype "passive"))
      (node (ref "R61") (pin "1") (pinfunction "1_1") (pintype "passive"))
      (node (ref "R61") (pin "2") (pinfunction "2_2") (pintype "passive"))
      (node (ref "R62") (pin "1") (pinfunction "1_1") (pintype "passive"))
      (node (ref "R62") (pin "2") (pinfunction "2_2") (pintype "passive"))
      (node (ref "R9") (pin "1") (pinfunction "1_1") (pintype "passive"))
    )
    (net (code "2") (name "/5V_USB") (class "Default")
      (node (ref "H2") (pin "52") (pinfunction "52_52") (pintype "passive"))
      (node (ref "PS1") (pin "1") (pinfunction "1_1") (pintype "bidirectional"))
    )
    (net (code "3") (name "/5V_USB_OTG") (class "Default")
      (node (ref "C3") (pin "2") (pinfunction "2_2") (pintype "passive"))
      (node (ref "IC7") (pin "59") (pinfunction "USB_OTG1_VBUS_59") (pintype "bidirectional"))
    )
    (net (code "4") (name "/ANT_BURN_WIRE1") (class "Default")
      (node (ref "H1") (pin "23") (pinfunction "23_23") (pintype "passive"))
      (node (ref "IC7") (pin "83") (pinfunction "GPIO_AD_B1_07_83") (pintype "bidirectional"))
    )
    (net (code "5") (name "/ANT_BURN_WIRE2") (class "Default")
      (node (ref "H1") (pin "25") (pinfunction "25_25") (pintype "passive"))
      (node (ref "IC7") (pin "78") (pinfunction "GPIO_AD_B1_12_78") (pintype "bidirectional"))
    )
    (net (code "6") (name "/CHASSIS") (class "Default")
      (node (ref "R64") (pin "2") (pinfunction "2_2") (pintype "passive"))
      (node (ref "R65") (pin "2") (pinfunction "2_2") (pintype "passive"))
      (node (ref "R66") (pin "2") (pinfunction "2_2") (pintype "passive"))
      (node (ref "R67") (pin "2") (pinfunction "2_2") (pintype "passive"))
    )
    (net (code "7") (name "/DCDC_OUT") (class "Default")
      (node (ref "C25") (pin "2") (pinfunction "2_2") (pintype "passive"))
      (node (ref "C26") (pin "2") (pinfunction "2_2") (pintype "passive"))
      (node (ref "C27") (pin "2") (pinfunction "2_2") (pintype "passive"))
      (node (ref "C28") (pin "2") (pinfunction "2_2") (pintype "passive"))
      (node (ref "C29") (pin "2") (pinfunction "2_2") (pintype "passive"))
      (node (ref "C30") (pin "2") (pinfunction "2_2") (pintype "passive"))
      (node (ref "C31") (pin "2") (pinfunction "2_2") (pintype "passive"))
      (node (ref "C33") (pin "2") (pinfunction "2_2") (pintype "passive"))
      (node (ref "C34") (pin "2") (pinfunction "2_2") (pintype "passive"))
      (node (ref "C35") (pin "2") (pinfunction "2_2") (pintype "passive"))
      (node (ref "C45") (pin "2") (pinfunction "2_2") (pintype "passive"))
      (node (ref "C46") (pin "2") (pinfunction "2_2") (pintype "passive"))
      (node (ref "IC7") (pin "102") (pinfunction "VDD_SOC_IN_5_102") (pintype "bidirectional"))
      (node (ref "IC7") (pin "114") (pinfunction "VDD_SOC_IN_6_114") (pintype "bidirectional"))
      (node (ref "IC7") (pin "134") (pinfunction "VDD_SOC_IN_7_134") (pintype "bidirectional"))
      (node (ref "IC7") (pin "31") (pinfunction "VDD_SOC_IN_2_31") (pintype "bidirectional"))
      (node (ref "IC7") (pin "39") (pinfunction "VDD_SOC_IN_3_39") (pintype "bidirectional"))
      (node (ref "IC7") (pin "5") (pinfunction "VDD_SOC_IN_1_5") (pintype "bidirectional"))
      (node (ref "IC7") (pin "86") (pinfunction "VDD_SOC_IN_4_86") (pintype "bidirectional"))
      (node (ref "L2") (pin "1") (pinfunction "1_1") (pintype "bidirectional"))
    )
    (net (code "8") (name "/DTR") (class "Default")
      (node (ref "H1") (pin "5") (pinfunction "5_5") (pintype "passive"))
      (node (ref "IC7") (pin "26") (pinfunction "GPIO_SD_B1_05_26") (pintype "bidirectional"))
    )
    (net (code "9") (name "/FLEXSPI_CLK") (class "Default")
      (node (ref "IC10") (pin "6") (pinfunction "SCK_6") (pintype "bidirectional"))
      (node (ref "IC7") (pin "24") (pinfunction "GPIO_SD_B1_07_24") (pintype "bidirectional"))
    )
    (net (code "10") (name "/FLEXSPI_D0_A") (class "Default")
      (node (ref "IC10") (pin "5") (pinfunction "SI_(IO0)_5") (pintype "bidirectional"))
      (node (ref "IC7") (pin "23") (pinfunction "GPIO_SD_B1_08_23") (pintype "bidirectional"))
    )
    (net (code "11") (name "/FLEXSPI_D1_A") (class "Default")
      (node (ref "IC10") (pin "2") (pinfunction "SO_(IO1)_2") (pintype "bidirectional"))
      (node (ref "IC7") (pin "21") (pinfunction "GPIO_SD_B1_10_21") (pintype "bidirectional"))
    )
    (net (code "12") (name "/FLEXSPI_D2_A") (class "Default")
      (node (ref "IC10") (pin "3") (pinfunction "WP#_(IO2)_3") (pintype "bidirectional"))
      (node (ref "IC7") (pin "22") (pinfunction "GPIO_SD_B1_09_22") (pintype "bidirectional"))
    )
    (net (code "13") (name "/FLEXSPI_D3_A") (class "Default")
      (node (ref "IC10") (pin "7") (pinfunction "HOLD#_(IO3)_7") (pintype "bidirectional"))
      (node (ref "IC7") (pin "25") (pinfunction "GPIO_SD_B1_06_25") (pintype "bidirectional"))
    )
    (net (code "14") (name "/FLEXSPI_SS0") (class "Default")
      (node (ref "IC10") (pin "1") (pinfunction "CE#_1") (pintype "bidirectional"))
      (node (ref "IC7") (pin "19") (pinfunction "GPIO_SD_B1_11_19") (pintype "bidirectional"))
      (node (ref "R1") (pin "2") (pinfunction "2_2") (pintype "passive"))
    )
    (net (code "15") (name "/GPANAIO") (class "Default")
      (node (ref "IC7") (pin "71") (pinfunction "GPANAIO_71") (pintype "bidirectional"))
      (node (ref "TP7") (pin "TP") (pinfunction "TP_TP") (pintype "input"))
    )
    (net (code "16") (name "/I2C1_SCL") (class "Default")
      (node (ref "H1") (pin "44") (pinfunction "44_44") (pintype "passive"))
      (node (ref "IC7") (pin "75") (pinfunction "GPIO_AD_B1_14_75") (pintype "bidirectional"))
    )
    (net (code "17") (name "/I2C1_SDA") (class "Default")
      (node (ref "H1") (pin "42") (pinfunction "42_42") (pintype "passive"))
      (node (ref "IC7") (pin "74") (pinfunction "GPIO_AD_B1_15_74") (pintype "bidirectional"))
    )
    (net (code "18") (name "/I2C2_SCL") (class "Default")
      (node (ref "H1") (pin "37") (pinfunction "37_37") (pintype "passive"))
      (node (ref "IC7") (pin "82") (pinfunction "GPIO_AD_B1_08_82") (pintype "bidirectional"))
    )
    (net (code "19") (name "/I2C2_SDA") (class "Default")
      (node (ref "H1") (pin "35") (pinfunction "35_35") (pintype "passive"))
      (node (ref "IC7") (pin "81") (pinfunction "GPIO_AD_B1_09_81") (pintype "bidirectional"))
    )
    (net (code "20") (name "/I2C3_SCL") (class "Default")
      (node (ref "H1") (pin "51") (pinfunction "51_51") (pintype "passive"))
      (node (ref "IC7") (pin "100") (pinfunction "GPIO_AD_B0_08_100") (pintype "bidirectional"))
    )
    (net (code "21") (name "/I2C3_SDA") (class "Default")
      (node (ref "H1") (pin "49") (pinfunction "49_49") (pintype "passive"))
      (node (ref "IC7") (pin "99") (pinfunction "GPIO_AD_B0_09_99") (pintype "bidirectional"))
    )
    (net (code "22") (name "/JTAG_DACK") (class "Default")
      (node (ref "J2") (pin "13") (pinfunction "13_13") (pintype "bidirectional"))
      (node (ref "R26") (pin "1") (pinfunction "1_1") (pintype "passive"))
    )
    (net (code "23") (name "/JTAG_DE") (class "Default")
      (node (ref "J2") (pin "6") (pinfunction "6_6") (pintype "bidirectional"))
    )
    (net (code "24") (name "/JTAG_MOD") (class "Default")
      (node (ref "IC7") (pin "109") (pinfunction "GPIO_AD_B0_02_109") (pintype "bidirectional"))
      (node (ref "R2") (pin "2") (pinfunction "2_2") (pintype "passive"))
    )
    (net (code "25") (name "/JTAG_NSRST") (class "Default")
      (node (ref "D2") (pin "1") (pinfunction "K_1") (pintype "bidirectional"))
      (node (ref "J2") (pin "12") (pinfunction "12_12") (pintype "bidirectional"))
    )
    (net (code "26") (name "/JTAG_NTRST") (class "Default")
      (node (ref "IC7") (pin "106") (pinfunction "GPIO_AD_B0_05_106") (pintype "bidirectional"))
      (node (ref "J2") (pin "9") (pinfunction "9_9") (pintype "bidirectional"))
      (node (ref "R63") (pin "2") (pinfunction "2_2") (pintype "passive"))
    )
    (net (code "27") (name "/JTAG_RTCK") (class "Default")
      (node (ref "J2") (pin "11") (pinfunction "11_11") (pintype "bidirectional"))
    )
    (net (code "28") (name "/JTAG_TCK") (class "Default")
      (node (ref "IC7") (pin "110") (pinfunction "GPIO_AD_B0_01_110") (pintype "bidirectional"))
      (node (ref "J2") (pin "4") (pinfunction "4_4") (pintype "bidirectional"))
    )
    (net (code "29") (name "/JTAG_TDI") (class "Default")
      (node (ref "IC7") (pin "108") (pinfunction "GPIO_AD_B0_03_108") (pintype "bidirectional"))
      (node (ref "J2") (pin "3") (pinfunction "3_3") (pintype "bidirectional"))
    )
    (net (code "30") (name "/JTAG_TDO") (class "Default")
      (node (ref "IC7") (pin "107") (pinfunction "GPIO_AD_B0_04_107") (pintype "bidirectional"))
      (node (ref "J2") (pin "5") (pinfunction "5_5") (pintype "bidirectional"))
    )
    (net (code "31") (name "/JTAG_TMS") (class "Default")
      (node (ref "IC7") (pin "111") (pinfunction "GPIO_AD_B0_00_111") (pintype "bidirectional"))
      (node (ref "J2") (pin "10") (pinfunction "10_10") (pintype "bidirectional"))
    )
    (net (code "32") (name "/NVCC_PLL") (class "Default")
      (node (ref "C22") (pin "2") (pinfunction "2_2") (pintype "passive"))
      (node (ref "IC7") (pin "72") (pinfunction "NVCC_PLL_72") (pintype "bidirectional"))
    )
    (net (code "33") (name "/PMIC_STBY_REQ") (class "Default")
      (node (ref "IC7") (pin "54") (pinfunction "PMIC_STBY_REQ_54") (pintype "bidirectional"))
      (node (ref "TP6") (pin "TP") (pinfunction "TP_TP") (pintype "input"))
    )
    (net (code "34") (name "/POR_B") (class "Default")
      (node (ref "C36") (pin "2") (pinfunction "2_2") (pintype "passive"))
      (node (ref "D2") (pin "2") (pinfunction "A_2") (pintype "bidirectional"))
      (node (ref "D4") (pin "1") (pinfunction "K_1") (pintype "bidirectional"))
      (node (ref "IC1") (pin "2") (pinfunction "~{RESET}_2") (pintype "bidirectional"))
      (node (ref "IC7") (pin "50") (pinfunction "POR_B_50") (pintype "bidirectional"))
      (node (ref "R8") (pin "1") (pinfunction "1_1") (pintype "passive"))
      (node (ref "R8") (pin "2") (pinfunction "2_2") (pintype "passive"))
    )
    (net (code "35") (name "/RTC_XTALI") (class "Default")
      (node (ref "C41") (pin "2") (pinfunction "2_2") (pintype "passive"))
      (node (ref "IC7") (pin "57") (pinfunction "RTC_XTALI_57") (pintype "bidirectional"))
      (node (ref "Y2") (pin "1") (pinfunction "IN/OUT_1") (pintype "bidirectional"))
    )
    (net (code "36") (name "/RTC_XTALO") (class "Default")
      (node (ref "C42") (pin "2") (pinfunction "2_2") (pintype "passive"))
      (node (ref "IC7") (pin "58") (pinfunction "RTC_XTALO_58") (pintype "bidirectional"))
      (node (ref "Y2") (pin "2") (pinfunction "OUT/IN_2") (pintype "bidirectional"))
    )
    (net (code "37") (name "/SD1_CLK") (class "Default")
      (node (ref "IC7") (pin "45") (pinfunction "GPIO_SD_B0_03_45") (pintype "bidirectional"))
      (node (ref "J1") (pin "5") (pinfunction "CLK_5") (pintype "input"))
      (node (ref "R56") (pin "1") (pinfunction "1_1") (pintype "passive"))
      (node (ref "R56") (pin "2") (pinfunction "2_2") (pintype "passive"))
    )
    (net (code "38") (name "/SD1_CMD") (class "Default")
      (node (ref "IC7") (pin "46") (pinfunction "GPIO_SD_B0_02_46") (pintype "bidirectional"))
      (node (ref "J1") (pin "3") (pinfunction "CMD_3") (pintype "bidirectional"))
      (node (ref "R5") (pin "2") (pinfunction "2_2") (pintype "passive"))
      (node (ref "R55") (pin "1") (pinfunction "1_1") (pintype "passive"))
      (node (ref "R55") (pin "2") (pinfunction "2_2") (pintype "passive"))
    )
    (net (code "39") (name "/SD1_D0") (class "Default")
      (node (ref "IC7") (pin "43") (pinfunction "GPIO_SD_B0_04_43") (pintype "bidirectional"))
      (node (ref "J1") (pin "7") (pinfunction "DAT0_7") (pintype "bidirectional"))
      (node (ref "R57") (pin "1") (pinfunction "1_1") (pintype "passive"))
      (node (ref "R57") (pin "2") (pinfunction "2_2") (pintype "passive"))
      (node (ref "R6") (pin "2") (pinfunction "2_2") (pintype "passive"))
    )
    (net (code "40") (name "/SD1_D1") (class "Default")
      (node (ref "IC7") (pin "42") (pinfunction "GPIO_SD_B0_05_42") (pintype "bidirectional"))
      (node (ref "J1") (pin "8") (pinfunction "DAT1_8") (pintype "bidirectional"))
      (node (ref "R58") (pin "1") (pinfunction "1_1") (pintype "passive"))
      (node (ref "R58") (pin "2") (pinfunction "2_2") (pintype "passive"))
    )
    (net (code "41") (name "/SD1_D2") (class "Default")
      (node (ref "IC7") (pin "48") (pinfunction "GPIO_SD_B0_00_48") (pintype "bidirectional"))
      (node (ref "J1") (pin "1") (pinfunction "DATA2_1") (pintype "bidirectional"))
      (node (ref "R53") (pin "1") (pinfunction "1_1") (pintype "passive"))
      (node (ref "R53") (pin "2") (pinfunction "2_2") (pintype "passive"))
    )
    (net (code "42") (name "/SD1_D3") (class "Default")
      (node (ref "IC7") (pin "47") (pinfunction "GPIO_SD_B0_01_47") (pintype "bidirectional"))
      (node (ref "J1") (pin "2") (pinfunction "CD/DAT3_2") (pintype "bidirectional"))
      (node (ref "R54") (pin "1") (pinfunction "1_1") (pintype "passive"))
      (node (ref "R54") (pin "2") (pinfunction "2_2") (pintype "passive"))
    )
    (net (code "43") (name "/SDRAM_3V3") (class "Default")
      (node (ref "C10") (pin "1") (pinfunction "1_1") (pintype "passive"))
      (node (ref "C11") (pin "1") (pinfunction "1_1") (pintype "passive"))
      (node (ref "C12") (pin "1") (pinfunction "1_1") (pintype "passive"))
      (node (ref "C13") (pin "1") (pinfunction "1_1") (pintype "passive"))
      (node (ref "C6") (pin "1") (pinfunction "1_1") (pintype "passive"))
      (node (ref "C7") (pin "1") (pinfunction "1_1") (pintype "passive"))
      (node (ref "C8") (pin "1") (pinfunction "1_1") (pintype "passive"))
      (node (ref "C9") (pin "1") (pinfunction "1_1") (pintype "passive"))
      (node (ref "FB1") (pin "2") (pinfunction "2_2") (pintype "bidirectional"))
      (node (ref "IC9") (pin "1") (pinfunction "VDD_1_1") (pintype "bidirectional"))
      (node (ref "IC9") (pin "14") (pinfunction "VDD_2_14") (pintype "bidirectional"))
      (node (ref "IC9") (pin "27") (pinfunction "VDD_3_27") (pintype "bidirectional"))
      (node (ref "IC9") (pin "3") (pinfunction "VDDQ_1_3") (pintype "bidirectional"))
      (node (ref "IC9") (pin "43") (pinfunction "VDDQ_3_43") (pintype "bidirectional"))
      (node (ref "IC9") (pin "49") (pinfunction "VDDQ_4_49") (pintype "bidirectional"))
      (node (ref "IC9") (pin "9") (pinfunction "VDDQ_2_9") (pintype "bidirectional"))
    )
    (net (code "44") (name "/SD_CD_SW") (class "Default")
      (node (ref "IC7") (pin "41") (pinfunction "GPIO_SD_B0_06_41") (pintype "bidirectional"))
      (node (ref "J1") (pin "9") (pinfunction "9_9") (pintype "bidirectional"))
      (node (ref "R59") (pin "1") (pinfunction "1_1") (pintype "passive"))
    )
    (net (code "45") (name "/SD_PWREN") (class "Default")
      (node (ref "D3") (pin "1") (pinfunction "K_1") (pintype "bidirectional"))
      (node (ref "IC7") (pin "27") (pinfunction "GPIO_SD_B1_04_27") (pintype "bidirectional"))
      (node (ref "R7") (pin "1") (pinfunction "1_1") (pintype "passive"))
      (node (ref "R7") (pin "2") (pinfunction "2_2") (pintype "passive"))
    )
    (net (code "46") (name "/SEMC_A0") (class "Default")
      (node (ref "IC7") (pin "142") (pinfunction "GPIO_EMC_16_142") (pintype "bidirectional"))
      (node (ref "IC9") (pin "23") (pinfunction "A0_23") (pintype "bidirectional"))
      (node (ref "R49") (pin "1") (pinfunction "1_1") (pintype "passive"))
      (node (ref "R49") (pin "2") (pinfunction "2_2") (pintype "passive"))
    )
    (net (code "47") (name "/SEMC_A1") (class "Default")
      (node (ref "IC7") (pin "141") (pinfunction "GPIO_EMC_17_141") (pintype "bidirectional"))
      (node (ref "IC9") (pin "24") (pinfunction "A1_24") (pintype "bidirectional"))
      (node (ref "R50") (pin "1") (pinfunction "1_1") (pintype "passive"))
      (node (ref "R50") (pin "2") (pinfunction "2_2") (pintype "passive"))
    )
    (net (code "48") (name "/SEMC_A2") (class "Default")
      (node (ref "IC7") (pin "140") (pinfunction "GPIO_EMC_18_140") (pintype "bidirectional"))
      (node (ref "IC9") (pin "25") (pinfunction "A2_25") (pintype "bidirectional"))
      (node (ref "R51") (pin "1") (pinfunction "1_1") (pintype "passive"))
      (node (ref "R51") (pin "2") (pinfunction "2_2") (pintype "passive"))
    )
    (net (code "49") (name "/SEMC_A3") (class "Default")
      (node (ref "IC7") (pin "139") (pinfunction "GPIO_EMC_19_139") (pintype "bidirectional"))
      (node (ref "IC9") (pin "26") (pinfunction "A3_26") (pintype "bidirectional"))
      (node (ref "R52") (pin "1") (pinfunction "1_1") (pintype "passive"))
      (node (ref "R52") (pin "2") (pinfunction "2_2") (pintype "passive"))
    )
    (net (code "50") (name "/SEMC_A4") (class "Default")
      (node (ref "IC7") (pin "138") (pinfunction "GPIO_EMC_20_138") (pintype "bidirectional"))
      (node (ref "IC9") (pin "29") (pinfunction "A4_29") (pintype "bidirectional"))
      (node (ref "R32") (pin "1") (pinfunction "1_1") (pintype "passive"))
      (node (ref "R32") (pin "2") (pinfunction "2_2") (pintype "passive"))
    )
    (net (code "51") (name "/SEMC_A5") (class "Default")
      (node (ref "IC7") (pin "137") (pinfunction "GPIO_EMC_21_137") (pintype "bidirectional"))
      (node (ref "IC9") (pin "30") (pinfunction "A5_30") (pintype "bidirectional"))
      (node (ref "R31") (pin "1") (pinfunction "1_1") (pintype "passive"))
      (node (ref "R31") (pin "2") (pinfunction "2_2") (pintype "passive"))
    )
    (net (code "52") (name "/SEMC_A6") (class "Default")
      (node (ref "IC7") (pin "136") (pinfunction "GPIO_EMC_22_136") (pintype "bidirectional"))
      (node (ref "IC9") (pin "31") (pinfunction "A6_31") (pintype "bidirectional"))
      (node (ref "R30") (pin "1") (pinfunction "1_1") (pintype "passive"))
      (node (ref "R30") (pin "2") (pinfunction "2_2") (pintype "passive"))
    )
    (net (code "53") (name "/SEMC_A7") (class "Default")
      (node (ref "IC7") (pin "133") (pinfunction "GPIO_EMC_23_133") (pintype "bidirectional"))
      (node (ref "IC9") (pin "32") (pinfunction "A7_32") (pintype "bidirectional"))
      (node (ref "R29") (pin "1") (pinfunction "1_1") (pintype "passive"))
      (node (ref "R29") (pin "2") (pinfunction "2_2") (pintype "passive"))
    )
    (net (code "54") (name "/SEMC_A8") (class "Default")
      (node (ref "IC7") (pin "132") (pinfunction "GPIO_EMC_24_132") (pintype "bidirectional"))
      (node (ref "IC9") (pin "33") (pinfunction "A8_33") (pintype "bidirectional"))
      (node (ref "R28") (pin "1") (pinfunction "1_1") (pintype "passive"))
      (node (ref "R28") (pin "2") (pinfunction "2_2") (pintype "passive"))
    )
    (net (code "55") (name "/SEMC_A9") (class "Default")
      (node (ref "IC7") (pin "131") (pinfunction "GPIO_EMC_25_131") (pintype "bidirectional"))
      (node (ref "IC9") (pin "34") (pinfunction "A9_34") (pintype "bidirectional"))
      (node (ref "R25") (pin "1") (pinfunction "1_1") (pintype "passive"))
      (node (ref "R25") (pin "2") (pinfunction "2_2") (pintype "passive"))
    )
    (net (code "56") (name "/SEMC_A10") (class "Default")
      (node (ref "IC7") (pin "143") (pinfunction "GPIO_EMC_15_143") (pintype "bidirectional"))
      (node (ref "IC9") (pin "22") (pinfunction "A10_22") (pintype "bidirectional"))
      (node (ref "R48") (pin "1") (pinfunction "1_1") (pintype "passive"))
      (node (ref "R48") (pin "2") (pinfunction "2_2") (pintype "passive"))
    )
    (net (code "57") (name "/SEMC_A11") (class "Default")
      (node (ref "IC7") (pin "130") (pinfunction "GPIO_EMC_26_130") (pintype "bidirectional"))
      (node (ref "IC9") (pin "35") (pinfunction "A11_35") (pintype "bidirectional"))
      (node (ref "R24") (pin "1") (pinfunction "1_1") (pintype "passive"))
      (node (ref "R24") (pin "2") (pinfunction "2_2") (pintype "passive"))
    )
    (net (code "58") (name "/SEMC_A12") (class "Default")
      (node (ref "IC7") (pin "129") (pinfunction "GPIO_EMC_27_129") (pintype "bidirectional"))
      (node (ref "IC9") (pin "36") (pinfunction "A12_36") (pintype "bidirectional"))
      (node (ref "R23") (pin "1") (pinfunction "1_1") (pintype "passive"))
      (node (ref "R23") (pin "2") (pinfunction "2_2") (pintype "passive"))
    )
    (net (code "59") (name "/SEMC_BA0") (class "Default")
      (node (ref "IC7") (pin "2") (pinfunction "GPIO_EMC_13_2") (pintype "bidirectional"))
      (node (ref "IC9") (pin "20") (pinfunction "BA0_20") (pintype "bidirectional"))
      (node (ref "R46") (pin "1") (pinfunction "1_1") (pintype "passive"))
      (node (ref "R46") (pin "2") (pinfunction "2_2") (pintype "passive"))
    )
    (net (code "60") (name "/SEMC_BA1") (class "Default")
      (node (ref "IC7") (pin "1") (pinfunction "GPIO_EMC_14_1") (pintype "bidirectional"))
      (node (ref "IC9") (pin "21") (pinfunction "BA1_21") (pintype "bidirectional"))
      (node (ref "R47") (pin "1") (pinfunction "1_1") (pintype "passive"))
      (node (ref "R47") (pin "2") (pinfunction "2_2") (pintype "passive"))
    )
    (net (code "61") (name "/SEMC_CAS") (class "Default")
      (node (ref "IC7") (pin "7") (pinfunction "GPIO_EMC_10_7") (pintype "bidirectional"))
      (node (ref "IC9") (pin "17") (pinfunction "~{CAS}_17") (pintype "bidirectional"))
      (node (ref "R43") (pin "1") (pinfunction "1_1") (pintype "passive"))
      (node (ref "R43") (pin "2") (pinfunction "2_2") (pintype "passive"))
    )
    (net (code "62") (name "/SEMC_CKE") (class "Default")
      (node (ref "IC7") (pin "127") (pinfunction "GPIO_EMC_29_127") (pintype "bidirectional"))
      (node (ref "IC9") (pin "37") (pinfunction "CKE_37") (pintype "bidirectional"))
      (node (ref "R22") (pin "1") (pinfunction "1_1") (pintype "passive"))
      (node (ref "R22") (pin "2") (pinfunction "2_2") (pintype "passive"))
    )
    (net (code "63") (name "/SEMC_CLK") (class "Default")
      (node (ref "IC7") (pin "126") (pinfunction "GPIO_EMC_30_126") (pintype "bidirectional"))
      (node (ref "IC9") (pin "38") (pinfunction "CLK_38") (pintype "bidirectional"))
      (node (ref "R21") (pin "1") (pinfunction "1_1") (pintype "passive"))
      (node (ref "R21") (pin "2") (pinfunction "2_2") (pintype "passive"))
    )
    (net (code "64") (name "/SEMC_CS0") (class "Default")
      (node (ref "IC7") (pin "3") (pinfunction "GPIO_EMC_12_3") (pintype "bidirectional"))
      (node (ref "IC9") (pin "19") (pinfunction "~{CS}_19") (pintype "bidirectional"))
      (node (ref "R45") (pin "1") (pinfunction "1_1") (pintype "passive"))
      (node (ref "R45") (pin "2") (pinfunction "2_2") (pintype "passive"))
    )
    (net (code "65") (name "/SEMC_D0") (class "Default")
      (node (ref "IC7") (pin "18") (pinfunction "GPIO_EMC_00_18") (pintype "bidirectional"))
      (node (ref "IC9") (pin "2") (pinfunction "DQ0_2") (pintype "bidirectional"))
      (node (ref "R33") (pin "1") (pinfunction "1_1") (pintype "passive"))
      (node (ref "R33") (pin "2") (pinfunction "2_2") (pintype "passive"))
    )
    (net (code "66") (name "/SEMC_D1") (class "Default")
      (node (ref "IC7") (pin "17") (pinfunction "GPIO_EMC_01_17") (pintype "bidirectional"))
      (node (ref "IC9") (pin "4") (pinfunction "NC_1_4") (pintype "bidirectional"))
      (node (ref "R34") (pin "1") (pinfunction "1_1") (pintype "passive"))
      (node (ref "R34") (pin "2") (pinfunction "2_2") (pintype "passive"))
    )
    (net (code "67") (name "/SEMC_D2") (class "Default")
      (node (ref "IC7") (pin "16") (pinfunction "GPIO_EMC_02_16") (pintype "bidirectional"))
      (node (ref "IC9") (pin "5") (pinfunction "DQ1_5") (pintype "bidirectional"))
      (node (ref "R35") (pin "1") (pinfunction "1_1") (pintype "passive"))
      (node (ref "R35") (pin "2") (pinfunction "2_2") (pintype "passive"))
    )
    (net (code "68") (name "/SEMC_D3") (class "Default")
      (node (ref "IC7") (pin "15") (pinfunction "GPIO_EMC_03_15") (pintype "bidirectional"))
      (node (ref "IC9") (pin "7") (pinfunction "NC_2_7") (pintype "bidirectional"))
      (node (ref "R36") (pin "1") (pinfunction "1_1") (pintype "passive"))
      (node (ref "R36") (pin "2") (pinfunction "2_2") (pintype "passive"))
    )
    (net (code "69") (name "/SEMC_D4") (class "Default")
      (node (ref "IC7") (pin "14") (pinfunction "GPIO_EMC_04_14") (pintype "bidirectional"))
      (node (ref "IC9") (pin "8") (pinfunction "DQ2_8") (pintype "bidirectional"))
      (node (ref "R37") (pin "1") (pinfunction "1_1") (pintype "passive"))
      (node (ref "R37") (pin "2") (pinfunction "2_2") (pintype "passive"))
    )
    (net (code "70") (name "/SEMC_D5") (class "Default")
      (node (ref "IC7") (pin "13") (pinfunction "GPIO_EMC_05_13") (pintype "bidirectional"))
      (node (ref "IC9") (pin "10") (pinfunction "NC_3_10") (pintype "bidirectional"))
      (node (ref "R38") (pin "1") (pinfunction "1_1") (pintype "passive"))
      (node (ref "R38") (pin "2") (pinfunction "2_2") (pintype "passive"))
    )
    (net (code "71") (name "/SEMC_D6") (class "Default")
      (node (ref "IC7") (pin "12") (pinfunction "GPIO_EMC_06_12") (pintype "bidirectional"))
      (node (ref "IC9") (pin "11") (pinfunction "DQ3_11") (pintype "bidirectional"))
      (node (ref "R39") (pin "1") (pinfunction "1_1") (pintype "passive"))
      (node (ref "R39") (pin "2") (pinfunction "2_2") (pintype "passive"))
    )
    (net (code "72") (name "/SEMC_D7") (class "Default")
      (node (ref "IC7") (pin "10") (pinfunction "GPIO_EMC_07_10") (pintype "bidirectional"))
      (node (ref "IC9") (pin "13") (pinfunction "NC_4_13") (pintype "bidirectional"))
      (node (ref "R40") (pin "1") (pinfunction "1_1") (pintype "passive"))
      (node (ref "R40") (pin "2") (pinfunction "2_2") (pintype "passive"))
    )
    (net (code "73") (name "/SEMC_D8") (class "Default")
      (node (ref "IC7") (pin "124") (pinfunction "GPIO_EMC_32_124") (pintype "bidirectional"))
      (node (ref "IC9") (pin "42") (pinfunction "NC_7_42") (pintype "bidirectional"))
      (node (ref "R19") (pin "1") (pinfunction "1_1") (pintype "passive"))
      (node (ref "R19") (pin "2") (pinfunction "2_2") (pintype "passive"))
    )
    (net (code "74") (name "/SEMC_D9") (class "Default")
      (node (ref "IC7") (pin "123") (pinfunction "GPIO_EMC_33_123") (pintype "bidirectional"))
      (node (ref "IC9") (pin "44") (pinfunction "DQ4_44") (pintype "bidirectional"))
      (node (ref "R18") (pin "1") (pinfunction "1_1") (pintype "passive"))
      (node (ref "R18") (pin "2") (pinfunction "2_2") (pintype "passive"))
    )
    (net (code "75") (name "/SEMC_D10") (class "Default")
      (node (ref "IC7") (pin "122") (pinfunction "GPIO_EMC_34_122") (pintype "bidirectional"))
      (node (ref "IC9") (pin "45") (pinfunction "NC_8_45") (pintype "bidirectional"))
      (node (ref "R17") (pin "1") (pinfunction "1_1") (pintype "passive"))
      (node (ref "R17") (pin "2") (pinfunction "2_2") (pintype "passive"))
    )
    (net (code "76") (name "/SEMC_D11") (class "Default")
      (node (ref "IC7") (pin "121") (pinfunction "GPIO_EMC_35_121") (pintype "bidirectional"))
      (node (ref "IC9") (pin "47") (pinfunction "DQ5_47") (pintype "bidirectional"))
      (node (ref "R16") (pin "1") (pinfunction "1_1") (pintype "passive"))
      (node (ref "R16") (pin "2") (pinfunction "2_2") (pintype "passive"))
    )
    (net (code "77") (name "/SEMC_D12") (class "Default")
      (node (ref "IC7") (pin "120") (pinfunction "GPIO_EMC_36_120") (pintype "bidirectional"))
      (node (ref "IC9") (pin "48") (pinfunction "NC_9_48") (pintype "bidirectional"))
      (node (ref "R15") (pin "1") (pinfunction "1_1") (pintype "passive"))
      (node (ref "R15") (pin "2") (pinfunction "2_2") (pintype "passive"))
    )
    (net (code "78") (name "/SEMC_D13") (class "Default")
      (node (ref "IC7") (pin "119") (pinfunction "GPIO_EMC_37_119") (pintype "bidirectional"))
      (node (ref "IC9") (pin "50") (pinfunction "DQ6_50") (pintype "bidirectional"))
      (node (ref "R14") (pin "1") (pinfunction "1_1") (pintype "passive"))
      (node (ref "R14") (pin "2") (pinfunction "2_2") (pintype "passive"))
    )
    (net (code "79") (name "/SEMC_D14") (class "Default")
      (node (ref "IC7") (pin "118") (pinfunction "GPIO_EMC_38_118") (pintype "bidirectional"))
      (node (ref "IC9") (pin "51") (pinfunction "NC_10_51") (pintype "bidirectional"))
      (node (ref "R13") (pin "1") (pinfunction "1_1") (pintype "passive"))
      (node (ref "R13") (pin "2") (pinfunction "2_2") (pintype "passive"))
    )
    (net (code "80") (name "/SEMC_D15") (class "Default")
      (node (ref "IC7") (pin "117") (pinfunction "GPIO_EMC_39_117") (pintype "bidirectional"))
      (node (ref "IC9") (pin "53") (pinfunction "DQ7_53") (pintype "bidirectional"))
      (node (ref "R12") (pin "1") (pinfunction "1_1") (pintype "passive"))
      (node (ref "R12") (pin "2") (pinfunction "2_2") (pintype "passive"))
    )
    (net (code "81") (name "/SEMC_DM0") (class "Default")
      (node (ref "IC7") (pin "9") (pinfunction "GPIO_EMC_08_9") (pintype "bidirectional"))
      (node (ref "IC9") (pin "15") (pinfunction "NC_5_15") (pintype "bidirectional"))
      (node (ref "R41") (pin "1") (pinfunction "1_1") (pintype "passive"))
      (node (ref "R41") (pin "2") (pinfunction "2_2") (pintype "passive"))
    )
    (net (code "82") (name "/SEMC_DM1") (class "Default")
      (node (ref "IC7") (pin "125") (pinfunction "GPIO_EMC_31_125") (pintype "bidirectional"))
      (node (ref "IC9") (pin "39") (pinfunction "DQM_39") (pintype "bidirectional"))
      (node (ref "R20") (pin "1") (pinfunction "1_1") (pintype "passive"))
      (node (ref "R20") (pin "2") (pinfunction "2_2") (pintype "passive"))
    )
    (net (code "83") (name "/SEMC_RAS") (class "Default")
      (node (ref "IC7") (pin "4") (pinfunction "GPIO_EMC_11_4") (pintype "bidirectional"))
      (node (ref "IC9") (pin "18") (pinfunction "~{RAS}_18") (pintype "bidirectional"))
      (node (ref "R44") (pin "1") (pinfunction "1_1") (pintype "passive"))
      (node (ref "R44") (pin "2") (pinfunction "2_2") (pintype "passive"))
    )
    (net (code "84") (name "/SEMC_WE") (class "Default")
      (node (ref "IC7") (pin "8") (pinfunction "GPIO_EMC_09_8") (pintype "bidirectional"))
      (node (ref "IC9") (pin "16") (pinfunction "~{WE}_16") (pintype "bidirectional"))
      (node (ref "R42") (pin "1") (pinfunction "1_1") (pintype "passive"))
      (node (ref "R42") (pin "2") (pinfunction "2_2") (pintype "passive"))
    )
    (net (code "85") (name "/SPI1_EN0") (class "Default")
      (node (ref "H1") (pin "9") (pinfunction "9_9") (pintype "passive"))
      (node (ref "IC7") (pin "92") (pinfunction "GPIO_AD_B1_00_92") (pintype "bidirectional"))
    )
    (net (code "86") (name "/SPI1_EN1") (class "Default")
      (node (ref "H1") (pin "10") (pinfunction "10_10") (pintype "passive"))
      (node (ref "IC7") (pin "91") (pinfunction "GPIO_AD_B1_01_91") (pintype "bidirectional"))
    )
    (net (code "87") (name "/SPI1_EN2") (class "Default")
      (node (ref "H1") (pin "22") (pinfunction "22_22") (pintype "passive"))
      (node (ref "IC7") (pin "90") (pinfunction "GPIO_AD_B1_02_90") (pintype "bidirectional"))
    )
    (net (code "88") (name "/SPI1_EN3") (class "Default")
      (node (ref "H1") (pin "21") (pinfunction "21_21") (pintype "passive"))
      (node (ref "IC7") (pin "89") (pinfunction "GPIO_AD_B1_03_89") (pintype "bidirectional"))
    )
    (net (code "89") (name "/SPI1_MISO") (class "Default")
      (node (ref "H1") (pin "18") (pinfunction "18_18") (pintype "passive"))
      (node (ref "IC7") (pin "95") (pinfunction "GPIO_AD_B0_13_95") (pintype "bidirectional"))
    )
    (net (code "90") (name "/SPI1_MOSI") (class "Default")
      (node (ref "H1") (pin "16") (pinfunction "16_16") (pintype "passive"))
      (node (ref "IC7") (pin "96") (pinfunction "GPIO_AD_B0_12_96") (pintype "bidirectional"))
    )
    (net (code "91") (name "/SPI1_PCS0") (class "Default")
      (node (ref "H1") (pin "7") (pinfunction "7_7") (pintype "passive"))
      (node (ref "IC7") (pin "97") (pinfunction "GPIO_AD_B0_11_97") (pintype "bidirectional"))
    )
    (net (code "92") (name "/SPI1_PCS1") (class "Default")
      (node (ref "H1") (pin "8") (pinfunction "8_8") (pintype "passive"))
      (node (ref "IC7") (pin "88") (pinfunction "GPIO_AD_B1_04_88") (pintype "bidirectional"))
    )
    (net (code "93") (name "/SPI1_PCS2") (class "Default")
      (node (ref "H1") (pin "20") (pinfunction "20_20") (pintype "passive"))
      (node (ref "IC7") (pin "87") (pinfunction "GPIO_AD_B1_05_87") (pintype "bidirectional"))
    )
    (net (code "94") (name "/SPI1_PCS3") (class "Default")
      (node (ref "H1") (pin "19") (pinfunction "19_19") (pintype "passive"))
      (node (ref "IC7") (pin "84") (pinfunction "GPIO_AD_B1_06_84") (pintype "bidirectional"))
    )
    (net (code "95") (name "/SPI1_SCK") (class "Default")
      (node (ref "H1") (pin "12") (pinfunction "12_12") (pintype "passive"))
      (node (ref "IC7") (pin "98") (pinfunction "GPIO_AD_B0_10_98") (pintype "bidirectional"))
    )
    (net (code "96") (name "/UART1_RX") (class "Default")
      (node (ref "H1") (pin "4") (pinfunction "4_4") (pintype "passive"))
      (node (ref "IC7") (pin "101") (pinfunction "GPIO_AD_B0_07_101") (pintype "bidirectional"))
    )
    (net (code "97") (name "/UART1_TX") (class "Default")
      (node (ref "H1") (pin "2") (pinfunction "2_2") (pintype "passive"))
      (node (ref "IC7") (pin "105") (pinfunction "GPIO_AD_B0_06_105") (pintype "bidirectional"))
    )
    (net (code "98") (name "/UART3_RX") (class "Default")
      (node (ref "H1") (pin "52") (pinfunction "52_52") (pintype "passive"))
      (node (ref "IC7") (pin "93") (pinfunction "GPIO_AD_B0_15_93") (pintype "bidirectional"))
    )
    (net (code "99") (name "/UART3_TX") (class "Default")
      (node (ref "H1") (pin "50") (pinfunction "50_50") (pintype "passive"))
      (node (ref "IC7") (pin "94") (pinfunction "GPIO_AD_B0_14_94") (pintype "bidirectional"))
    )
    (net (code "100") (name "/UART4_RX") (class "Default")
      (node (ref "H1") (pin "3") (pinfunction "3_3") (pintype "passive"))
      (node (ref "IC7") (pin "79") (pinfunction "GPIO_AD_B1_11_79") (pintype "bidirectional"))
    )
    (net (code "101") (name "/UART4_TX") (class "Default")
      (node (ref "H1") (pin "1") (pinfunction "1_1") (pintype "passive"))
      (node (ref "IC7") (pin "80") (pinfunction "GPIO_AD_B1_10_80") (pintype "bidirectional"))
    )
    (net (code "102") (name "/USB_OTG1_CHD") (class "Default")
      (node (ref "IC7") (pin "66") (pinfunction "USB_OTG1_CHD_B_66") (pintype "bidirectional"))
      (node (ref "TP5") (pin "TP") (pinfunction "TP_TP") (pintype "input"))
    )
    (net (code "103") (name "/USER_LED") (class "Default")
      (node (ref "D11") (pin "1") (pinfunction "CATHODE_1") (pintype "passive"))
      (node (ref "R63") (pin "1") (pinfunction "1_1") (pintype "passive"))
    )
    (net (code "104") (name "/VDD_HIGH_CAP") (class "Default")
      (node (ref "C23") (pin "2") (pinfunction "2_2") (pintype "passive"))
      (node (ref "C24") (pin "2") (pinfunction "2_2") (pintype "passive"))
      (node (ref "IC7") (pin "65") (pinfunction "VDD_HIGH_CAP_65") (pintype "bidirectional"))
    )
    (net (code "105") (name "/VDD_SNVS_CAP") (class "Default")
      (node (ref "C21") (pin "2") (pinfunction "2_2") (pintype "passive"))
      (node (ref "IC7") (pin "56") (pinfunction "VDD_SNVS_CAP_56") (pintype "bidirectional"))
    )
    (net (code "106") (name "/VDD_USB_3V") (class "Default")
      (node (ref "C14") (pin "2") (pinfunction "2_2") (pintype "passive"))
      (node (ref "C4") (pin "2") (pinfunction "2_2") (pintype "passive"))
      (node (ref "IC7") (pin "61") (pinfunction "VDD_USB_CAP_61") (pintype "bidirectional"))
    )
    (net (code "107") (name "/VSD_3V3") (class "Default")
      (node (ref "C38") (pin "2") (pinfunction "2_2") (pintype "passive"))
      (node (ref "C49") (pin "2") (pinfunction "2_2") (pintype "passive"))
      (node (ref "C52") (pin "2") (pinfunction "2_2") (pintype "passive"))
      (node (ref "IC8") (pin "3") (pinfunction "VOUT_3") (pintype "bidirectional"))
      (node (ref "J1") (pin "4") (pinfunction "VDD_4") (pintype "power_in"))
    )
    (net (code "108") (name "/WAKEUP") (class "Default")
      (node (ref "IC7") (pin "52") (pinfunction "WAKEUP_52") (pintype "bidirectional"))
      (node (ref "TP8") (pin "TP") (pinfunction "TP_TP") (pintype "input"))
    )
    (net (code "109") (name "/XTALI") (class "Default")
      (node (ref "C39") (pin "2") (pinfunction "2_2") (pintype "passive"))
      (node (ref "IC7") (pin "67") (pinfunction "XTALI_67") (pintype "bidirectional"))
      (node (ref "R10") (pin "1") (pinfunction "1_1") (pintype "passive"))
      (node (ref "Y1") (pin "3") (pinfunction "XTAL_2_3") (pintype "bidirectional"))
    )
    (net (code "110") (name "/XTALO") (class "Default")
      (node (ref "C40") (pin "2") (pinfunction "2_2") (pintype "passive"))
      (node (ref "IC7") (pin "68") (pinfunction "XTALO_68") (pintype "bidirectional"))
      (node (ref "Y1") (pin "1") (pinfunction "XTAL_1_1") (pintype "bidirectional"))
    )
    (net (code "111") (name "GND") (class "Default")
      (node (ref "C1") (pin "1") (pinfunction "1_1") (pintype "passive"))
      (node (ref "C10") (pin "2") (pinfunction "2_2") (pintype "passive"))
      (node (ref "C11") (pin "2") (pinfunction "2_2") (pintype "passive"))
      (node (ref "C12") (pin "2") (pinfunction "2_2") (pintype "passive"))
      (node (ref "C13") (pin "2") (pinfunction "2_2") (pintype "passive"))
      (node (ref "C14") (pin "1") (pinfunction "1_1") (pintype "passive"))
      (node (ref "C15") (pin "1") (pinfunction "1_1") (pintype "passive"))
      (node (ref "C16") (pin "1") (pinfunction "1_1") (pintype "passive"))
      (node (ref "C17") (pin "1") (pinfunction "1_1") (pintype "passive"))
      (node (ref "C18") (pin "1") (pinfunction "1_1") (pintype "passive"))
      (node (ref "C19") (pin "1") (pinfunction "1_1") (pintype "passive"))
      (node (ref "C2") (pin "1") (pinfunction "1_1") (pintype "passive"))
      (node (ref "C20") (pin "1") (pinfunction "1_1") (pintype "passive"))
      (node (ref "C21") (pin "1") (pinfunction "1_1") (pintype "passive"))
      (node (ref "C22") (pin "1") (pinfunction "1_1") (pintype "passive"))
      (node (ref "C23") (pin "1") (pinfunction "1_1") (pintype "passive"))
      (node (ref "C24") (pin "1") (pinfunction "1_1") (pintype "passive"))
      (node (ref "C25") (pin "1") (pinfunction "1_1") (pintype "passive"))
      (node (ref "C26") (pin "1") (pinfunction "1_1") (pintype "passive"))
      (node (ref "C27") (pin "1") (pinfunction "1_1") (pintype "passive"))
      (node (ref "C28") (pin "1") (pinfunction "1_1") (pintype "passive"))
      (node (ref "C29") (pin "1") (pinfunction "1_1") (pintype "passive"))
      (node (ref "C3") (pin "1") (pinfunction "1_1") (pintype "passive"))
      (node (ref "C30") (pin "1") (pinfunction "1_1") (pintype "passive"))
      (node (ref "C31") (pin "1") (pinfunction "1_1") (pintype "passive"))
      (node (ref "C32") (pin "1") (pinfunction "1_1") (pintype "passive"))
      (node (ref "C33") (pin "1") (pinfunction "1_1") (pintype "passive"))
      (node (ref "C34") (pin "1") (pinfunction "1_1") (pintype "passive"))
      (node (ref "C35") (pin "1") (pinfunction "1_1") (pintype "passive"))
      (node (ref "C36") (pin "1") (pinfunction "1_1") (pintype "passive"))
      (node (ref "C37") (pin "1") (pinfunction "1_1") (pintype "passive"))
      (node (ref "C38") (pin "1") (pinfunction "1_1") (pintype "passive"))
      (node (ref "C39") (pin "1") (pinfunction "1_1") (pintype "passive"))
      (node (ref "C4") (pin "1") (pinfunction "1_1") (pintype "passive"))
      (node (ref "C40") (pin "1") (pinfunction "1_1") (pintype "passive"))
      (node (ref "C41") (pin "1") (pinfunction "1_1") (pintype "passive"))
      (node (ref "C42") (pin "1") (pinfunction "1_1") (pintype "passive"))
      (node (ref "C43") (pin "1") (pinfunction "1_1") (pintype "passive"))
      (node (ref "C44") (pin "1") (pinfunction "1_1") (pintype "passive"))
      (node (ref "C45") (pin "1") (pinfunction "1_1") (pintype "passive"))
      (node (ref "C46") (pin "1") (pinfunction "1_1") (pintype "passive"))
      (node (ref "C47") (pin "1") (pinfunction "1_1") (pintype "passive"))
      (node (ref "C48") (pin "1") (pinfunction "1_1") (pintype "passive"))
      (node (ref "C49") (pin "1") (pinfunction "1_1") (pintype "passive"))
      (node (ref "C5") (pin "1") (pinfunction "1_1") (pintype "passive"))
      (node (ref "C50") (pin "1") (pinfunction "1_1") (pintype "passive"))
      (node (ref "C51") (pin "1") (pinfunction "1_1") (pintype "passive"))
      (node (ref "C52") (pin "1") (pinfunction "1_1") (pintype "passive"))
      (node (ref "C53") (pin "1") (pinfunction "1_1") (pintype "passive"))
      (node (ref "C54") (pin "1") (pinfunction "1_1") (pintype "passive"))
      (node (ref "C55") (pin "1") (pinfunction "1_1") (pintype "passive"))
      (node (ref "C56") (pin "1") (pinfunction "1_1") (pintype "passive"))
      (node (ref "C57") (pin "1") (pinfunction "1_1") (pintype "passive"))
      (node (ref "C58") (pin "1") (pinfunction "1_1") (pintype "passive"))
      (node (ref "C59") (pin "1") (pinfunction "1_1") (pintype "passive"))
      (node (ref "C6") (pin "2") (pinfunction "2_2") (pintype "passive"))
      (node (ref "C60") (pin "1") (pinfunction "1_1") (pintype "passive"))
      (node (ref "C61") (pin "1") (pinfunction "1_1") (pintype "passive"))
      (node (ref "C62") (pin "1") (pinfunction "1_1") (pintype "passive"))
      (node (ref "C63") (pin "1") (pinfunction "1_1") (pintype "passive"))
      (node (ref "C64") (pin "1") (pinfunction "1_1") (pintype "passive"))
      (node (ref "C7") (pin "2") (pinfunction "2_2") (pintype "passive"))
      (node (ref "C8") (pin "2") (pinfunction "2_2") (pintype "passive"))
      (node (ref "C9") (pin "2") (pinfunction "2_2") (pintype "passive"))
      (node (ref "H2") (pin "10") (pinfunction "10_10") (pintype "passive"))
      (node (ref "H2") (pin "13") (pinfunction "13_13") (pintype "passive"))
      (node (ref "H2") (pin "18") (pinfunction "18_18") (pintype "passive"))
      (node (ref "H2") (pin "21") (pinfunction "21_21") (pintype "passive"))
      (node (ref "H2") (pin "22") (pinfunction "22_22") (pintype "passive"))
      (node (ref "H2") (pin "29") (pinfunction "29_29") (pintype "passive"))
      (node (ref "H2") (pin "30") (pinfunction "30_30") (pintype "passive"))
      (node (ref "H2") (pin "31") (pinfunction "31_31") (pintype "passive"))
      (node (ref "H2") (pin "47") (pinfunction "47_47") (pintype "passive"))
      (node (ref "H2") (pin "48") (pinfunction "48_48") (pintype "passive"))
      (node (ref "IC1") (pin "1") (pinfunction "GND_1") (pintype "bidirectional"))
      (node (ref "IC10") (pin "4") (pinfunction "GND_4") (pintype "bidirectional"))
      (node (ref "IC7") (pin "103") (pinfunction "VSS_6_103") (pintype "bidirectional"))
      (node (ref "IC7") (pin "113") (pinfunction "VSS_7_113") (pintype "bidirectional"))
      (node (ref "IC7") (pin "135") (pinfunction "VSS_8_135") (pintype "bidirectional"))
      (node (ref "IC7") (pin "35") (pinfunction "DCDC_GND_35") (pintype "bidirectional"))
      (node (ref "IC7") (pin "40") (pinfunction "VSS_2_40") (pintype "bidirectional"))
      (node (ref "IC7") (pin "51") (pinfunction "TEST_MODE_51") (pintype "bidirectional"))
      (node (ref "IC7") (pin "6") (pinfunction "VSS_1_6") (pintype "bidirectional"))
      (node (ref "IC7") (pin "60") (pinfunction "VSS_3_60") (pintype "bidirectional"))
      (node (ref "IC7") (pin "64") (pinfunction "NGND_KEL0_64") (pintype "bidirectional"))
      (node (ref "IC7") (pin "70") (pinfunction "VSS_4_70") (pintype "bidirectional"))
      (node (ref "IC7") (pin "85") (pinfunction "VSS_5_85") (pintype "bidirectional"))
      (node (ref "IC8") (pin "2") (pinfunction "GND_2") (pintype "bidirectional"))
      (node (ref "IC8") (pin "5") (pinfunction "EP_5") (pintype "bidirectional"))
      (node (ref "IC9") (pin "12") (pinfunction "VSSQ_2_12") (pintype "bidirectional"))
      (node (ref "IC9") (pin "28") (pinfunction "VSS_1_28") (pintype "bidirectional"))
      (node (ref "IC9") (pin "41") (pinfunction "VSS_2_41") (pintype "bidirectional"))
      (node (ref "IC9") (pin "46") (pinfunction "VSSQ_3_46") (pintype "bidirectional"))
      (node (ref "IC9") (pin "52") (pinfunction "VSSQ_4_52") (pintype "bidirectional"))
      (node (ref "IC9") (pin "54") (pinfunction "VSS_3_54") (pintype "bidirectional"))
      (node (ref "IC9") (pin "6") (pinfunction "VSSQ_1_6") (pintype "bidirectional"))
      (node (ref "J1") (pin "10") (pinfunction "10_10") (pintype "bidirectional"))
      (node (ref "J1") (pin "11") (pinfunction "11_11") (pintype "bidirectional"))
      (node (ref "J1") (pin "12") (pinfunction "12_12") (pintype "bidirectional"))
      (node (ref "J1") (pin "13") (pinfunction "13_13") (pintype "bidirectional"))
      (node (ref "J1") (pin "14") (pinfunction "14_14") (pintype "bidirectional"))
      (node (ref "J1") (pin "15") (pinfunction "15_15") (pintype "bidirectional"))
      (node (ref "J1") (pin "16") (pinfunction "16_16") (pintype "bidirectional"))
      (node (ref "J1") (pin "6") (pinfunction "VSS_6") (pintype "power_in"))
      (node (ref "J2") (pin "1") (pinfunction "1_1") (pintype "bidirectional"))
      (node (ref "J2") (pin "14") (pinfunction "14_14") (pintype "bidirectional"))
      (node (ref "J2") (pin "7") (pinfunction "7_7") (pintype "bidirectional"))
      (node (ref "PS1") (pin "2") (pinfunction "2_2") (pintype "bidirectional"))
      (node (ref "R10") (pin "2") (pinfunction "2_2") (pintype "passive"))
      (node (ref "R2") (pin "1") (pinfunction "1_1") (pintype "passive"))
      (node (ref "R26") (pin "2") (pinfunction "2_2") (pintype "passive"))
      (node (ref "R64") (pin "1") (pinfunction "1_1") (pintype "passive"))
      (node (ref "R65") (pin "1") (pinfunction "1_1") (pintype "passive"))
      (node (ref "R66") (pin "1") (pinfunction "1_1") (pintype "passive"))
      (node (ref "R67") (pin "1") (pinfunction "1_1") (pintype "passive"))
      (node (ref "Y1") (pin "2") (pinfunction "NC_1_2") (pintype "bidirectional"))
      (node (ref "Y1") (pin "4") (pinfunction "NC_2_4") (pintype "bidirectional"))
    )
    (net (code "112") (name "Net-(D1-K)") (class "Default")
      (node (ref "C20") (pin "2") (pinfunction "2_2") (pintype "passive"))
      (node (ref "D1") (pin "1") (pinfunction "K_1") (pintype "bidirectional"))
      (node (ref "IC7") (pin "55") (pinfunction "VDD_SNVS_IN_55") (pintype "bidirectional"))
    )
    (net (code "113") (name "Net-(IC1-VDD)") (class "Default")
      (node (ref "IC1") (pin "3") (pinfunction "VDD_3") (pintype "bidirectional"))
      (node (ref "R9") (pin "2") (pinfunction "2_2") (pintype "passive"))
    )
    (net (code "114") (name "Net-(IC7-DCDC_LP)") (class "Default")
      (node (ref "IC7") (pin "36") (pinfunction "DCDC_LP_36") (pintype "bidirectional"))
      (node (ref "L2") (pin "2") (pinfunction "2_2") (pintype "bidirectional"))
    )
    (net (code "115") (name "Net-(IC7-DCDC_PSWITCH)") (class "Default")
      (node (ref "C44") (pin "2") (pinfunction "2_2") (pintype "passive"))
      (node (ref "IC7") (pin "37") (pinfunction "DCDC_PSWITCH_37") (pintype "bidirectional"))
      (node (ref "R11") (pin "1") (pinfunction "1_1") (pintype "passive"))
    )
    (net (code "116") (name "Net-(J2-Pad2)") (class "Default")
      (node (ref "J2") (pin "2") (pinfunction "2_2") (pintype "bidirectional"))
      (node (ref "R27") (pin "1") (pinfunction "1_1") (pintype "passive"))
    )
    (net (code "117") (name "unconnected-(H1-Pad6)") (class "Default")
      (node (ref "H1") (pin "6") (pinfunction "6_6") (pintype "passive"))
    )
    (net (code "118") (name "unconnected-(H1-Pad11)") (class "Default")
      (node (ref "H1") (pin "11") (pinfunction "11_11") (pintype "passive"))
    )
    (net (code "119") (name "unconnected-(H1-Pad13)") (class "Default")
      (node (ref "H1") (pin "13") (pinfunction "13_13") (pintype "passive"))
    )
    (net (code "120") (name "unconnected-(H1-Pad14)") (class "Default")
      (node (ref "H1") (pin "14") (pinfunction "14_14") (pintype "passive"))
    )
    (net (code "121") (name "unconnected-(H1-Pad15)") (class "Default")
      (node (ref "H1") (pin "15") (pinfunction "15_15") (pintype "passive"))
    )
    (net (code "122") (name "unconnected-(H1-Pad17)") (class "Default")
      (node (ref "H1") (pin "17") (pinfunction "17_17") (pintype "passive"))
    )
    (net (code "123") (name "unconnected-(H1-Pad24)") (class "Default")
      (node (ref "H1") (pin "24") (pinfunction "24_24") (pintype "passive"))
    )
    (net (code "124") (name "unconnected-(H1-Pad26)") (class "Default")
      (node (ref "H1") (pin "26") (pinfunction "26_26") (pintype "passive"))
    )
    (net (code "125") (name "unconnected-(H1-Pad27)") (class "Default")
      (node (ref "H1") (pin "27") (pinfunction "27_27") (pintype "passive"))
    )
    (net (code "126") (name "unconnected-(H1-Pad28)") (class "Default")
      (node (ref "H1") (pin "28") (pinfunction "28_28") (pintype "passive"))
    )
    (net (code "127") (name "unconnected-(H1-Pad29)") (class "Default")
      (node (ref "H1") (pin "29") (pinfunction "29_29") (pintype "passive"))
    )
    (net (code "128") (name "unconnected-(H1-Pad30)") (class "Default")
      (node (ref "H1") (pin "30") (pinfunction "30_30") (pintype "passive"))
    )
    (net (code "129") (name "unconnected-(H1-Pad31)") (class "Default")
      (node (ref "H1") (pin "31") (pinfunction "31_31") (pintype "passive"))
    )
    (net (code "130") (name "unconnected-(H1-Pad32)") (class "Default")
      (node (ref "H1") (pin "32") (pinfunction "32_32") (pintype "passive"))
    )
    (net (code "131") (name "unconnected-(H1-Pad33)") (class "Default")
      (node (ref "H1") (pin "33") (pinfunction "33_33") (pintype "passive"))
    )
    (net (code "132") (name "unconnected-(H1-Pad34)") (class "Default")
      (node (ref "H1") (pin "34") (pinfunction "34_34") (pintype "passive"))
    )
    (net (code "133") (name "unconnected-(H1-Pad36)") (class "Default")
      (node (ref "H1") (pin "36") (pinfunction "36_36") (pintype "passive"))
    )
    (net (code "134") (name "unconnected-(H1-Pad38)") (class "Default")
      (node (ref "H1") (pin "38") (pinfunction "38_38") (pintype "passive"))
    )
    (net (code "135") (name "unconnected-(H1-Pad39)") (class "Default")
      (node (ref "H1") (pin "39") (pinfunction "39_39") (pintype "passive"))
    )
    (net (code "136") (name "unconnected-(H1-Pad40)") (class "Default")
      (node (ref "H1") (pin "40") (pinfunction "40_40") (pintype "passive"))
    )
    (net (code "137") (name "unconnected-(H1-Pad41)") (class "Default")
      (node (ref "H1") (pin "41") (pinfunction "41_41") (pintype "passive"))
    )
    (net (code "138") (name "unconnected-(H1-Pad43)") (class "Default")
      (node (ref "H1") (pin "43") (pinfunction "43_43") (pintype "passive"))
    )
    (net (code "139") (name "unconnected-(H1-Pad45)") (class "Default")
      (node (ref "H1") (pin "45") (pinfunction "45_45") (pintype "passive"))
    )
    (net (code "140") (name "unconnected-(H1-Pad46)") (class "Default")
      (node (ref "H1") (pin "46") (pinfunction "46_46") (pintype "passive"))
    )
    (net (code "141") (name "unconnected-(H1-Pad47)") (class "Default")
      (node (ref "H1") (pin "47") (pinfunction "47_47") (pintype "passive"))
    )
    (net (code "142") (name "unconnected-(H1-Pad48)") (class "Default")
      (node (ref "H1") (pin "48") (pinfunction "48_48") (pintype "passive"))
    )
    (net (code "143") (name "unconnected-(H2-Pad1)") (class "Default")
      (node (ref "H2") (pin "1") (pinfunction "1_1") (pintype "passive"))
    )
    (net (code "144") (name "unconnected-(H2-Pad2)") (class "Default")
      (node (ref "H2") (pin "2") (pinfunction "2_2") (pintype "passive"))
    )
    (net (code "145") (name "unconnected-(H2-Pad3)") (class "Default")
      (node (ref "H2") (pin "3") (pinfunction "3_3") (pintype "passive"))
    )
    (net (code "146") (name "unconnected-(H2-Pad4)") (class "Default")
      (node (ref "H2") (pin "4") (pinfunction "4_4") (pintype "passive"))
    )
    (net (code "147") (name "unconnected-(H2-Pad5)") (class "Default")
      (node (ref "H2") (pin "5") (pinfunction "5_5") (pintype "passive"))
    )
    (net (code "148") (name "unconnected-(H2-Pad6)") (class "Default")
      (node (ref "H2") (pin "6") (pinfunction "6_6") (pintype "passive"))
    )
    (net (code "149") (name "unconnected-(H2-Pad7)") (class "Default")
      (node (ref "H2") (pin "7") (pinfunction "7_7") (pintype "passive"))
    )
    (net (code "150") (name "unconnected-(H2-Pad8)") (class "Default")
      (node (ref "H2") (pin "8") (pinfunction "8_8") (pintype "passive"))
    )
    (net (code "151") (name "unconnected-(H2-Pad9)") (class "Default")
      (node (ref "H2") (pin "9") (pinfunction "9_9") (pintype "passive"))
    )
    (net (code "152") (name "unconnected-(H2-Pad11)") (class "Default")
      (node (ref "H2") (pin "11") (pinfunction "11_11") (pintype "passive"))
    )
    (net (code "153") (name "unconnected-(H2-Pad12)") (class "Default")
      (node (ref "H2") (pin "12") (pinfunction "12_12") (pintype "passive"))
    )
    (net (code "154") (name "unconnected-(H2-Pad14)") (class "Default")
      (node (ref "H2") (pin "14") (pinfunction "14_14") (pintype "passive"))
    )
    (net (code "155") (name "unconnected-(H2-Pad15)") (class "Default")
      (node (ref "H2") (pin "15") (pinfunction "15_15") (pintype "passive"))
    )
    (net (code "156") (name "unconnected-(H2-Pad16)") (class "Default")
      (node (ref "H2") (pin "16") (pinfunction "16_16") (pintype "passive"))
    )
    (net (code "157") (name "unconnected-(H2-Pad17)") (class "Default")
      (node (ref "H2") (pin "17") (pinfunction "17_17") (pintype "passive"))
    )
    (net (code "158") (name "unconnected-(H2-Pad19)") (class "Default")
      (node (ref "H2") (pin "19") (pinfunction "19_19") (pintype "passive"))
    )
    (net (code "159") (name "unconnected-(H2-Pad20)") (class "Default")
      (node (ref "H2") (pin "20") (pinfunction "20_20") (pintype "passive"))
    )
    (net (code "160") (name "unconnected-(H2-Pad23)") (class "Default")
      (node (ref "H2") (pin "23") (pinfunction "23_23") (pintype "passive"))
    )
    (net (code "161") (name "unconnected-(H2-Pad24)") (class "Default")
      (node (ref "H2") (pin "24") (pinfunction "24_24") (pintype "passive"))
    )
    (net (code "162") (name "unconnected-(H2-Pad25)") (class "Default")
      (node (ref "H2") (pin "25") (pinfunction "25_25") (pintype "passive"))
    )
    (net (code "163") (name "unconnected-(H2-Pad26)") (class "Default")
      (node (ref "H2") (pin "26") (pinfunction "26_26") (pintype "passive"))
    )
    (net (code "164") (name "unconnected-(H2-Pad32)") (class "Default")
      (node (ref "H2") (pin "32") (pinfunction "32_32") (pintype "passive"))
    )
    (net (code "165") (name "unconnected-(H2-Pad33)") (class "Default")
      (node (ref "H2") (pin "33") (pinfunction "33_33") (pintype "passive"))
    )
    (net (code "166") (name "unconnected-(H2-Pad34)") (class "Default")
      (node (ref "H2") (pin "34") (pinfunction "34_34") (pintype "passive"))
    )
    (net (code "167") (name "unconnected-(H2-Pad35)") (class "Default")
      (node (ref "H2") (pin "35") (pinfunction "35_35") (pintype "passive"))
    )
    (net (code "168") (name "unconnected-(H2-Pad36)") (class "Default")
      (node (ref "H2") (pin "36") (pinfunction "36_36") (pintype "passive"))
    )
    (net (code "169") (name "unconnected-(H2-Pad37)") (class "Default")
      (node (ref "H2") (pin "37") (pinfunction "37_37") (pintype "passive"))
    )
    (net (code "170") (name "unconnected-(H2-Pad38)") (class "Default")
      (node (ref "H2") (pin "38") (pinfunction "38_38") (pintype "passive"))
    )
    (net (code "171") (name "unconnected-(H2-Pad39)") (class "Default")
      (node (ref "H2") (pin "39") (pinfunction "39_39") (pintype "passive"))
    )
    (net (code "172") (name "unconnected-(H2-Pad40)") (class "Default")
      (node (ref "H2") (pin "40") (pinfunction "40_40") (pintype "passive"))
    )
    (net (code "173") (name "unconnected-(H2-Pad41)") (class "Default")
      (node (ref "H2") (pin "41") (pinfunction "41_41") (pintype "passive"))
    )
    (net (code "174") (name "unconnected-(H2-Pad42)") (class "Default")
      (node (ref "H2") (pin "42") (pinfunction "42_42") (pintype "passive"))
    )
    (net (code "175") (name "unconnected-(H2-Pad43)") (class "Default")
      (node (ref "H2") (pin "43") (pinfunction "43_43") (pintype "passive"))
    )
    (net (code "176") (name "unconnected-(H2-Pad44)") (class "Default")
      (node (ref "H2") (pin "44") (pinfunction "44_44") (pintype "passive"))
    )
    (net (code "177") (name "unconnected-(H2-Pad45)") (class "Default")
      (node (ref "H2") (pin "45") (pinfunction "45_45") (pintype "passive"))
    )
    (net (code "178") (name "unconnected-(H2-Pad46)") (class "Default")
      (node (ref "H2") (pin "46") (pinfunction "46_46") (pintype "passive"))
    )
    (net (code "179") (name "unconnected-(H2-Pad49)") (class "Default")
      (node (ref "H2") (pin "49") (pinfunction "49_49") (pintype "passive"))
    )
    (net (code "180") (name "unconnected-(H2-Pad50)") (class "Default")
      (node (ref "H2") (pin "50") (pinfunction "50_50") (pintype "passive"))
    )
    (net (code "181") (name "unconnected-(H2-Pad51)") (class "Default")
      (node (ref "H2") (pin "51") (pinfunction "51_51") (pintype "passive"))
    )
    (net (code "182") (name "unconnected-(IC7-GPIO_AD_B1_13-Pad76)") (class "Default")
      (node (ref "IC7") (pin "76") (pinfunction "GPIO_AD_B1_13_76") (pintype "bidirectional"))
    )
    (net (code "183") (name "unconnected-(IC7-GPIO_EMC_28-Pad128)") (class "Default")
      (node (ref "IC7") (pin "128") (pinfunction "GPIO_EMC_28_128") (pintype "bidirectional"))
    )
    (net (code "184") (name "unconnected-(IC7-GPIO_EMC_40-Pad116)") (class "Default")
      (node (ref "IC7") (pin "116") (pinfunction "GPIO_EMC_40_116") (pintype "bidirectional"))
    )
    (net (code "185") (name "unconnected-(IC7-GPIO_EMC_41-Pad115)") (class "Default")
      (node (ref "IC7") (pin "115") (pinfunction "GPIO_EMC_41_115") (pintype "bidirectional"))
    )
    (net (code "186") (name "unconnected-(IC7-GPIO_SD_B1_00-Pad33)") (class "Default")
      (node (ref "IC7") (pin "33") (pinfunction "GPIO_SD_B1_00_33") (pintype "bidirectional"))
    )
    (net (code "187") (name "unconnected-(IC7-GPIO_SD_B1_01-Pad32)") (class "Default")
      (node (ref "IC7") (pin "32") (pinfunction "GPIO_SD_B1_01_32") (pintype "bidirectional"))
    )
    (net (code "188") (name "unconnected-(IC7-GPIO_SD_B1_02-Pad30)") (class "Default")
      (node (ref "IC7") (pin "30") (pinfunction "GPIO_SD_B1_02_30") (pintype "bidirectional"))
    )
    (net (code "189") (name "unconnected-(IC7-GPIO_SD_B1_03-Pad28)") (class "Default")
      (node (ref "IC7") (pin "28") (pinfunction "GPIO_SD_B1_03_28") (pintype "bidirectional"))
    )
    (net (code "190") (name "unconnected-(IC7-ONOFF-Pad49)") (class "Default")
      (node (ref "IC7") (pin "49") (pinfunction "ONOFF_49") (pintype "bidirectional"))
    )
    (net (code "191") (name "unconnected-(IC7-PMIC_ON_REQ-Pad53)") (class "Default")
      (node (ref "IC7") (pin "53") (pinfunction "PMIC_ON_REQ_53") (pintype "bidirectional"))
    )
    (net (code "192") (name "unconnected-(IC7-USB_OTG1_DN-Pad62)") (class "Default")
      (node (ref "IC7") (pin "62") (pinfunction "USB_OTG1_DN_62") (pintype "bidirectional"))
    )
    (net (code "193") (name "unconnected-(IC7-USB_OTG1_DP-Pad63)") (class "Default")
      (node (ref "IC7") (pin "63") (pinfunction "USB_OTG1_DP_63") (pintype "bidirectional"))
    )
    (net (code "194") (name "unconnected-(IC9-NC_6-Pad40)") (class "Default")
      (node (ref "IC9") (pin "40") (pinfunction "NC_6_40") (pintype "bidirectional"))
    )
    (net (code "195") (name "unconnected-(J2-PadMH1)") (class "Default")
      (node (ref "J2") (pin "MH1") (pinfunction "MH1_MH1") (pintype "bidirectional"))
    )
    (net (code "196") (name "unconnected-(J2-PadMH2)") (class "Default")
      (node (ref "J2") (pin "MH2") (pinfunction "MH2_MH2") (pintype "bidirectional"))
    )
    (net (code "197") (name "unconnected-(J2-PadMP1)") (class "Default")
      (node (ref "J2") (pin "MP1") (pinfunction "MP1_MP1") (pintype "bidirectional"))
    )
    (net (code "198") (name "unconnected-(J2-PadMP2)") (class "Default")
      (node (ref "J2") (pin "MP2") (pinfunction "MP2_MP2") (pintype "bidirectional"))
    )
    (net (code "199") (name "unconnected-(PS1-Pad3)") (class "Default")
      (node (ref "PS1") (pin "3") (pinfunction "3_3") (pintype "bidirectional"))
    )
  )
)
